# STHV800_pulser_board_v10.net
KiCad netlist of a schematic drawn in EAGLE
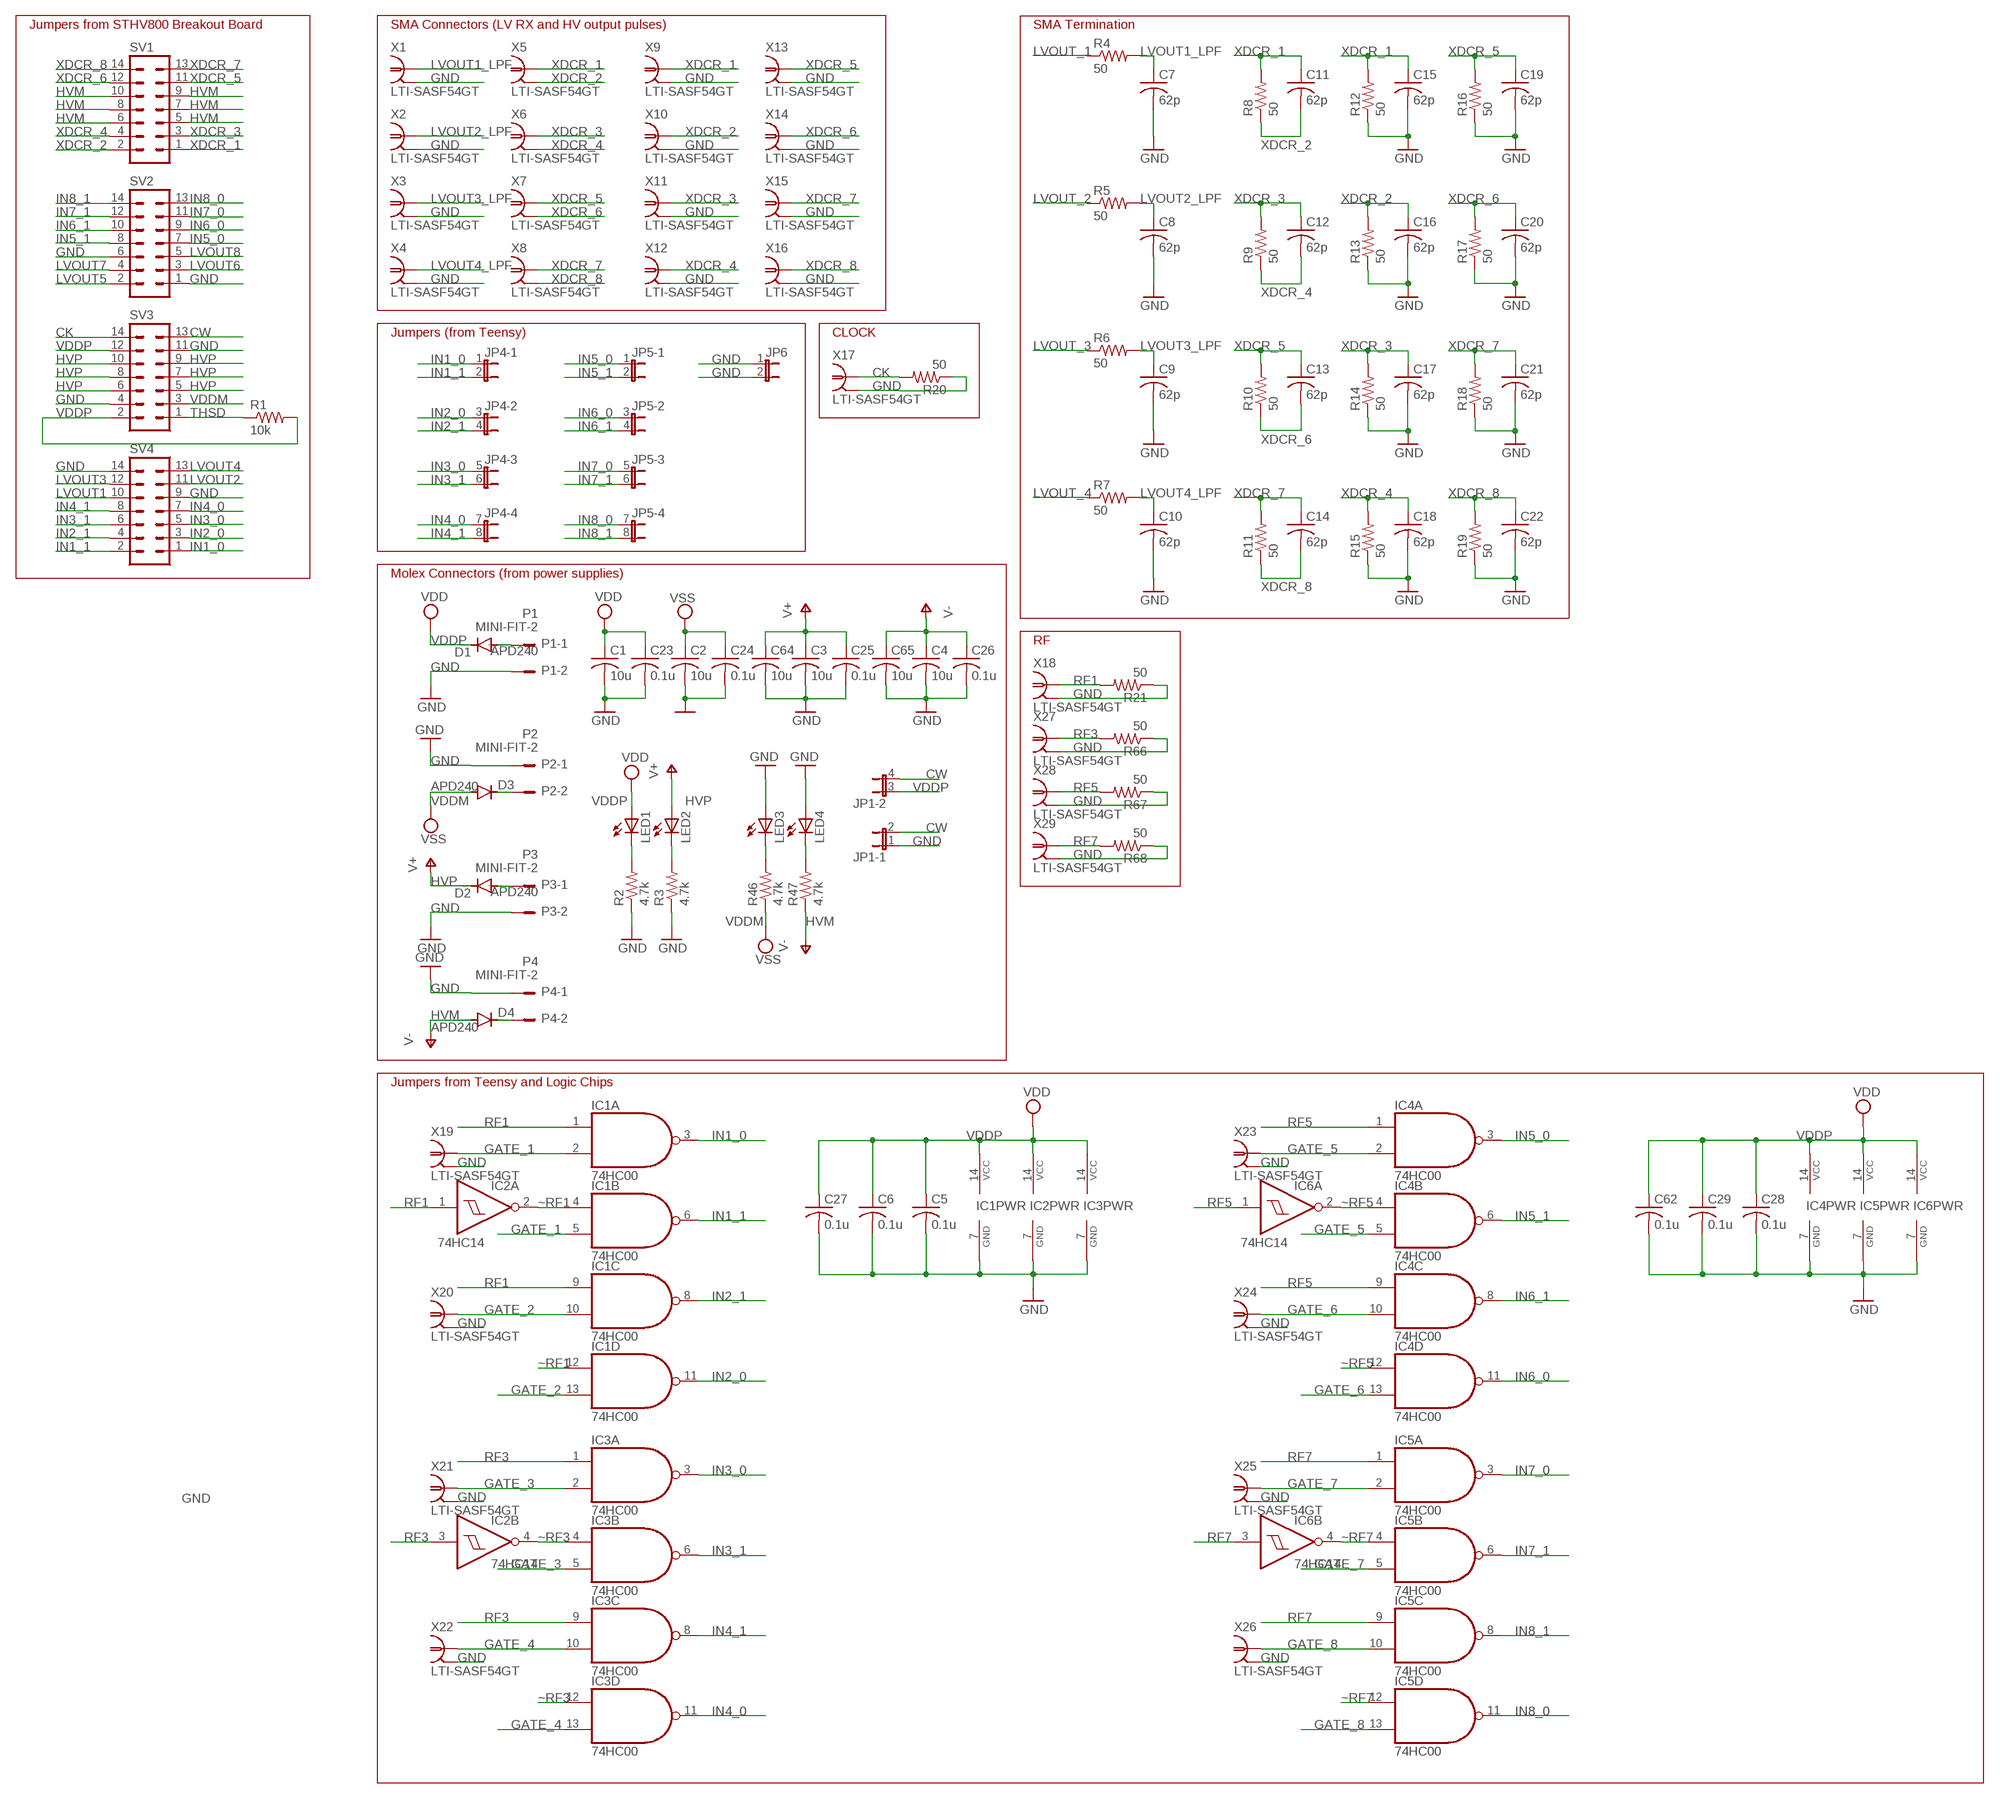
[diagram p0: schematic, sheet 1]
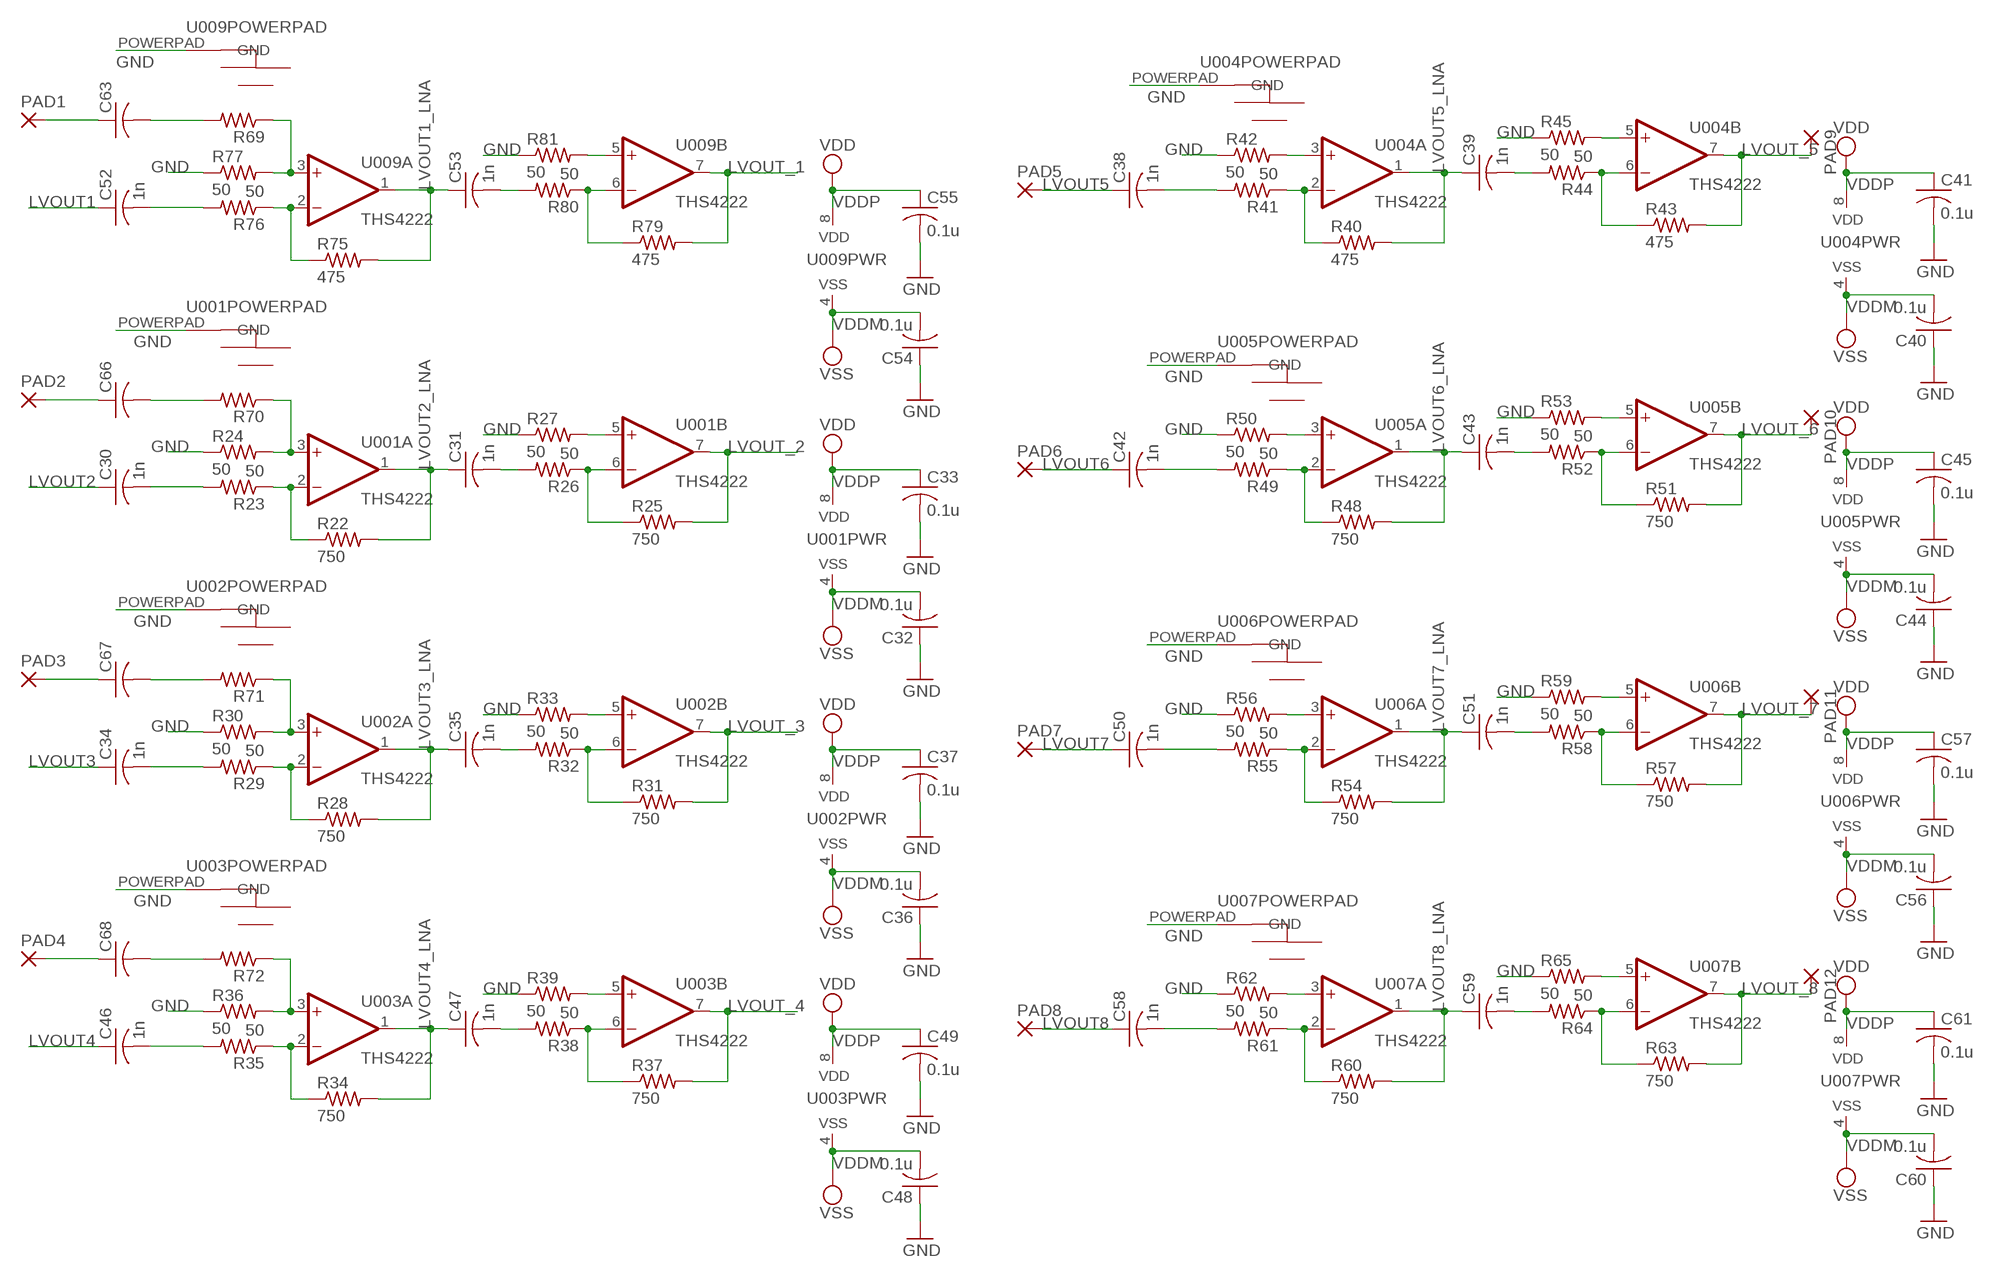
[diagram p1: schematic, sheet 2]

(export (version "E")
  (design (tool "Eeschema 10.0.6"))
  (components
    (comp (ref "C1")
      (value "10u")
      (footprint "eagle-import:C1206")
      (libsource (lib "eagle-import") (part "C-USC1206"))
    )
    (comp (ref "C2")
      (value "10u")
      (footprint "eagle-import:C1206")
      (libsource (lib "eagle-import") (part "C-USC1206"))
    )
    (comp (ref "C3")
      (value "10u")
      (footprint "eagle-import:C1210")
      (libsource (lib "eagle-import") (part "C-USC1210"))
    )
    (comp (ref "C4")
      (value "10u")
      (footprint "eagle-import:C1210")
      (libsource (lib "eagle-import") (part "C-USC1210"))
    )
    (comp (ref "C5")
      (value "0.1u")
      (footprint "eagle-import:C0805")
      (libsource (lib "eagle-import") (part "C-USC0805"))
    )
    (comp (ref "C6")
      (value "0.1u")
      (footprint "eagle-import:C0805")
      (libsource (lib "eagle-import") (part "C-USC0805"))
    )
    (comp (ref "C7")
      (value "62p")
      (footprint "eagle-import:C0805")
      (libsource (lib "eagle-import") (part "C-USC0805"))
    )
    (comp (ref "C8")
      (value "62p")
      (footprint "eagle-import:C0805")
      (libsource (lib "eagle-import") (part "C-USC0805"))
    )
    (comp (ref "C9")
      (value "62p")
      (footprint "eagle-import:C0805")
      (libsource (lib "eagle-import") (part "C-USC0805"))
    )
    (comp (ref "C10")
      (value "62p")
      (footprint "eagle-import:C0805")
      (libsource (lib "eagle-import") (part "C-USC0805"))
    )
    (comp (ref "C11")
      (value "62p")
      (footprint "eagle-import:C0805")
      (libsource (lib "eagle-import") (part "C-USC0805"))
    )
    (comp (ref "C12")
      (value "62p")
      (footprint "eagle-import:C0805")
      (libsource (lib "eagle-import") (part "C-USC0805"))
    )
    (comp (ref "C13")
      (value "62p")
      (footprint "eagle-import:C0805")
      (libsource (lib "eagle-import") (part "C-USC0805"))
    )
    (comp (ref "C14")
      (value "62p")
      (footprint "eagle-import:C0805")
      (libsource (lib "eagle-import") (part "C-USC0805"))
    )
    (comp (ref "C15")
      (value "62p")
      (footprint "eagle-import:C0805")
      (libsource (lib "eagle-import") (part "C-USC0805"))
    )
    (comp (ref "C16")
      (value "62p")
      (footprint "eagle-import:C0805")
      (libsource (lib "eagle-import") (part "C-USC0805"))
    )
    (comp (ref "C17")
      (value "62p")
      (footprint "eagle-import:C0805")
      (libsource (lib "eagle-import") (part "C-USC0805"))
    )
    (comp (ref "C18")
      (value "62p")
      (footprint "eagle-import:C0805")
      (libsource (lib "eagle-import") (part "C-USC0805"))
    )
    (comp (ref "C19")
      (value "62p")
      (footprint "eagle-import:C0805")
      (libsource (lib "eagle-import") (part "C-USC0805"))
    )
    (comp (ref "C20")
      (value "62p")
      (footprint "eagle-import:C0805")
      (libsource (lib "eagle-import") (part "C-USC0805"))
    )
    (comp (ref "C21")
      (value "62p")
      (footprint "eagle-import:C0805")
      (libsource (lib "eagle-import") (part "C-USC0805"))
    )
    (comp (ref "C22")
      (value "62p")
      (footprint "eagle-import:C0805")
      (libsource (lib "eagle-import") (part "C-USC0805"))
    )
    (comp (ref "C23")
      (value "0.1u")
      (footprint "eagle-import:C0805")
      (libsource (lib "eagle-import") (part "C-USC0805"))
    )
    (comp (ref "C24")
      (value "0.1u")
      (footprint "eagle-import:C0805")
      (libsource (lib "eagle-import") (part "C-USC0805"))
    )
    (comp (ref "C25")
      (value "0.1u")
      (footprint "eagle-import:C0805")
      (libsource (lib "eagle-import") (part "C-USC0805"))
    )
    (comp (ref "C26")
      (value "0.1u")
      (footprint "eagle-import:C0805")
      (libsource (lib "eagle-import") (part "C-USC0805"))
    )
    (comp (ref "C27")
      (value "0.1u")
      (footprint "eagle-import:C0805")
      (libsource (lib "eagle-import") (part "C-USC0805"))
    )
    (comp (ref "C28")
      (value "0.1u")
      (footprint "eagle-import:C0805")
      (libsource (lib "eagle-import") (part "C-USC0805"))
    )
    (comp (ref "C29")
      (value "0.1u")
      (footprint "eagle-import:C0805")
      (libsource (lib "eagle-import") (part "C-USC0805"))
    )
    (comp (ref "C62")
      (value "0.1u")
      (footprint "eagle-import:C0805")
      (libsource (lib "eagle-import") (part "C-USC0805"))
    )
    (comp (ref "C64")
      (value "10u")
      (footprint "eagle-import:C1210")
      (libsource (lib "eagle-import") (part "C-USC1210"))
    )
    (comp (ref "C65")
      (value "10u")
      (footprint "eagle-import:C1210")
      (libsource (lib "eagle-import") (part "C-USC1210"))
    )
    (comp (ref "D1")
      (value "APD240")
      (footprint "eagle-import:SOD-123_MINI-SMA")
      (libsource (lib "eagle-import") (part "CGRM400-G1"))
    )
    (comp (ref "D2")
      (value "APD240")
      (footprint "eagle-import:SOD-123_MINI-SMA")
      (libsource (lib "eagle-import") (part "CGRM400-G1"))
    )
    (comp (ref "D3")
      (value "APD240")
      (footprint "eagle-import:SOD-123_MINI-SMA")
      (libsource (lib "eagle-import") (part "CGRM400-G1"))
    )
    (comp (ref "D4")
      (value "APD240")
      (footprint "eagle-import:SOD-123_MINI-SMA")
      (libsource (lib "eagle-import") (part "CGRM400-G1"))
    )
    (comp (ref "IC1")
      (value "74HC00")
      (footprint "eagle-import:TSSOP14")
      (libsource (lib "eagle-import") (part "74HC00"))
    )
    (comp (ref "IC2")
      (value "74HC14")
      (footprint "eagle-import:TSSOP14")
      (libsource (lib "eagle-import") (part "74HC14"))
    )
    (comp (ref "IC3")
      (value "74HC00")
      (footprint "eagle-import:TSSOP14")
      (libsource (lib "eagle-import") (part "74HC00"))
    )
    (comp (ref "IC4")
      (value "74HC00")
      (footprint "eagle-import:TSSOP14")
      (libsource (lib "eagle-import") (part "74HC00"))
    )
    (comp (ref "IC5")
      (value "74HC00")
      (footprint "eagle-import:TSSOP14")
      (libsource (lib "eagle-import") (part "74HC00"))
    )
    (comp (ref "IC6")
      (value "74HC14")
      (footprint "eagle-import:TSSOP14")
      (libsource (lib "eagle-import") (part "74HC14"))
    )
    (comp (ref "JP1")
      (value "JP2QE")
      (footprint "eagle-import:JP2Q")
      (libsource (lib "eagle-import") (part "JP2QE"))
    )
    (comp (ref "JP4")
      (value "JP4QE")
      (footprint "eagle-import:JP4Q")
      (libsource (lib "eagle-import") (part "JP4QE"))
    )
    (comp (ref "JP5")
      (value "JP4QE")
      (footprint "eagle-import:JP4Q")
      (libsource (lib "eagle-import") (part "JP4QE"))
    )
    (comp (ref "JP6")
      (value "JP1E")
      (footprint "eagle-import:JP1")
      (libsource (lib "eagle-import") (part "JP1E"))
    )
    (comp (ref "LED1")
      (value "LEDSMT1206")
      (footprint "eagle-import:1206")
      (libsource (lib "eagle-import") (part "LEDSMT1206"))
    )
    (comp (ref "LED2")
      (value "LEDSMT1206")
      (footprint "eagle-import:1206")
      (libsource (lib "eagle-import") (part "LEDSMT1206"))
    )
    (comp (ref "LED3")
      (value "LEDSMT1206")
      (footprint "eagle-import:1206")
      (libsource (lib "eagle-import") (part "LEDSMT1206"))
    )
    (comp (ref "LED4")
      (value "LEDSMT1206")
      (footprint "eagle-import:1206")
      (libsource (lib "eagle-import") (part "LEDSMT1206"))
    )
    (comp (ref "P1")
      (value "MINI-FIT-2")
      (footprint "eagle-import:CON-MOLEX-MINI-FIT_39-30-_02_")
      (libsource (lib "eagle-import") (part "MINI-FIT-2"))
    )
    (comp (ref "P2")
      (value "MINI-FIT-2")
      (footprint "eagle-import:CON-MOLEX-MINI-FIT_39-30-_02_")
      (libsource (lib "eagle-import") (part "MINI-FIT-2"))
    )
    (comp (ref "P3")
      (value "MINI-FIT-2")
      (footprint "eagle-import:CON-MOLEX-MINI-FIT_39-30-_02_")
      (libsource (lib "eagle-import") (part "MINI-FIT-2"))
    )
    (comp (ref "P4")
      (value "MINI-FIT-2")
      (footprint "eagle-import:CON-MOLEX-MINI-FIT_39-30-_02_")
      (libsource (lib "eagle-import") (part "MINI-FIT-2"))
    )
    (comp (ref "R1")
      (value "10k")
      (footprint "eagle-import:R0805")
      (libsource (lib "eagle-import") (part "R-US_R0805"))
    )
    (comp (ref "R2")
      (value "4.7k")
      (footprint "eagle-import:R0805")
      (libsource (lib "eagle-import") (part "R-US_R0805"))
    )
    (comp (ref "R3")
      (value "4.7k")
      (footprint "eagle-import:R0805")
      (libsource (lib "eagle-import") (part "R-US_R0805"))
    )
    (comp (ref "R4")
      (value "50")
      (footprint "eagle-import:R1206")
      (libsource (lib "eagle-import") (part "R-US_R1206"))
    )
    (comp (ref "R5")
      (value "50")
      (footprint "eagle-import:R1206")
      (libsource (lib "eagle-import") (part "R-US_R1206"))
    )
    (comp (ref "R6")
      (value "50")
      (footprint "eagle-import:R1206")
      (libsource (lib "eagle-import") (part "R-US_R1206"))
    )
    (comp (ref "R7")
      (value "50")
      (footprint "eagle-import:R1206")
      (libsource (lib "eagle-import") (part "R-US_R1206"))
    )
    (comp (ref "R8")
      (value "50")
      (footprint "eagle-import:R1206")
      (libsource (lib "eagle-import") (part "R-US_R1206"))
    )
    (comp (ref "R9")
      (value "50")
      (footprint "eagle-import:R1206")
      (libsource (lib "eagle-import") (part "R-US_R1206"))
    )
    (comp (ref "R10")
      (value "50")
      (footprint "eagle-import:R1206")
      (libsource (lib "eagle-import") (part "R-US_R1206"))
    )
    (comp (ref "R11")
      (value "50")
      (footprint "eagle-import:R1206")
      (libsource (lib "eagle-import") (part "R-US_R1206"))
    )
    (comp (ref "R12")
      (value "50")
      (footprint "eagle-import:R1206")
      (libsource (lib "eagle-import") (part "R-US_R1206"))
    )
    (comp (ref "R13")
      (value "50")
      (footprint "eagle-import:R1206")
      (libsource (lib "eagle-import") (part "R-US_R1206"))
    )
    (comp (ref "R14")
      (value "50")
      (footprint "eagle-import:R1206")
      (libsource (lib "eagle-import") (part "R-US_R1206"))
    )
    (comp (ref "R15")
      (value "50")
      (footprint "eagle-import:R1206")
      (libsource (lib "eagle-import") (part "R-US_R1206"))
    )
    (comp (ref "R16")
      (value "50")
      (footprint "eagle-import:R1206")
      (libsource (lib "eagle-import") (part "R-US_R1206"))
    )
    (comp (ref "R17")
      (value "50")
      (footprint "eagle-import:R1206")
      (libsource (lib "eagle-import") (part "R-US_R1206"))
    )
    (comp (ref "R18")
      (value "50")
      (footprint "eagle-import:R1206")
      (libsource (lib "eagle-import") (part "R-US_R1206"))
    )
    (comp (ref "R19")
      (value "50")
      (footprint "eagle-import:R1206")
      (libsource (lib "eagle-import") (part "R-US_R1206"))
    )
    (comp (ref "R20")
      (value "50")
      (footprint "eagle-import:R0805")
      (libsource (lib "eagle-import") (part "R-US_R0805"))
    )
    (comp (ref "R21")
      (value "50")
      (footprint "eagle-import:R0805")
      (libsource (lib "eagle-import") (part "R-US_R0805"))
    )
    (comp (ref "R46")
      (value "4.7k")
      (footprint "eagle-import:R0805")
      (libsource (lib "eagle-import") (part "R-US_R0805"))
    )
    (comp (ref "R47")
      (value "4.7k")
      (footprint "eagle-import:R0805")
      (libsource (lib "eagle-import") (part "R-US_R0805"))
    )
    (comp (ref "R66")
      (value "50")
      (footprint "eagle-import:R0805")
      (libsource (lib "eagle-import") (part "R-US_R0805"))
    )
    (comp (ref "R67")
      (value "50")
      (footprint "eagle-import:R0805")
      (libsource (lib "eagle-import") (part "R-US_R0805"))
    )
    (comp (ref "R68")
      (value "50")
      (footprint "eagle-import:R0805")
      (libsource (lib "eagle-import") (part "R-US_R0805"))
    )
    (comp (ref "SV1")
      (value "MA07-2")
      (footprint "eagle-import:MA07-2")
      (libsource (lib "eagle-import") (part "MA07-2"))
    )
    (comp (ref "SV2")
      (value "MA07-2")
      (footprint "eagle-import:MA07-2")
      (libsource (lib "eagle-import") (part "MA07-2"))
    )
    (comp (ref "SV3")
      (value "MA07-2")
      (footprint "eagle-import:MA07-2")
      (libsource (lib "eagle-import") (part "MA07-2"))
    )
    (comp (ref "SV4")
      (value "MA07-2")
      (footprint "eagle-import:MA07-2")
      (libsource (lib "eagle-import") (part "MA07-2"))
    )
    (comp (ref "X1")
      (value "LTI-SASF54GT")
      (footprint "eagle-import:LTI-SASF54GT")
      (libsource (lib "eagle-import") (part "LTI-SASF54GT"))
    )
    (comp (ref "X2")
      (value "LTI-SASF54GT")
      (footprint "eagle-import:LTI-SASF54GT")
      (libsource (lib "eagle-import") (part "LTI-SASF54GT"))
    )
    (comp (ref "X3")
      (value "LTI-SASF54GT")
      (footprint "eagle-import:LTI-SASF54GT")
      (libsource (lib "eagle-import") (part "LTI-SASF54GT"))
    )
    (comp (ref "X4")
      (value "LTI-SASF54GT")
      (footprint "eagle-import:LTI-SASF54GT")
      (libsource (lib "eagle-import") (part "LTI-SASF54GT"))
    )
    (comp (ref "X5")
      (value "LTI-SASF54GT")
      (footprint "eagle-import:LTI-SASF54GT")
      (libsource (lib "eagle-import") (part "LTI-SASF54GT"))
    )
    (comp (ref "X6")
      (value "LTI-SASF54GT")
      (footprint "eagle-import:LTI-SASF54GT")
      (libsource (lib "eagle-import") (part "LTI-SASF54GT"))
    )
    (comp (ref "X7")
      (value "LTI-SASF54GT")
      (footprint "eagle-import:LTI-SASF54GT")
      (libsource (lib "eagle-import") (part "LTI-SASF54GT"))
    )
    (comp (ref "X8")
      (value "LTI-SASF54GT")
      (footprint "eagle-import:LTI-SASF54GT")
      (libsource (lib "eagle-import") (part "LTI-SASF54GT"))
    )
    (comp (ref "X9")
      (value "LTI-SASF54GT")
      (footprint "eagle-import:LTI-SASF54GT")
      (libsource (lib "eagle-import") (part "LTI-SASF54GT"))
    )
    (comp (ref "X10")
      (value "LTI-SASF54GT")
      (footprint "eagle-import:LTI-SASF54GT")
      (libsource (lib "eagle-import") (part "LTI-SASF54GT"))
    )
    (comp (ref "X11")
      (value "LTI-SASF54GT")
      (footprint "eagle-import:LTI-SASF54GT")
      (libsource (lib "eagle-import") (part "LTI-SASF54GT"))
    )
    (comp (ref "X12")
      (value "LTI-SASF54GT")
      (footprint "eagle-import:LTI-SASF54GT")
      (libsource (lib "eagle-import") (part "LTI-SASF54GT"))
    )
    (comp (ref "X13")
      (value "LTI-SASF54GT")
      (footprint "eagle-import:LTI-SASF54GT")
      (libsource (lib "eagle-import") (part "LTI-SASF54GT"))
    )
    (comp (ref "X14")
      (value "LTI-SASF54GT")
      (footprint "eagle-import:LTI-SASF54GT")
      (libsource (lib "eagle-import") (part "LTI-SASF54GT"))
    )
    (comp (ref "X15")
      (value "LTI-SASF54GT")
      (footprint "eagle-import:LTI-SASF54GT")
      (libsource (lib "eagle-import") (part "LTI-SASF54GT"))
    )
    (comp (ref "X16")
      (value "LTI-SASF54GT")
      (footprint "eagle-import:LTI-SASF54GT")
      (libsource (lib "eagle-import") (part "LTI-SASF54GT"))
    )
    (comp (ref "X17")
      (value "LTI-SASF54GT")
      (footprint "eagle-import:LTI-SASF54GT")
      (libsource (lib "eagle-import") (part "LTI-SASF54GT"))
    )
    (comp (ref "X18")
      (value "LTI-SASF54GT")
      (footprint "eagle-import:LTI-SASF54GT")
      (libsource (lib "eagle-import") (part "LTI-SASF54GT"))
    )
    (comp (ref "X19")
      (value "LTI-SASF54GT")
      (footprint "eagle-import:LTI-SASF54GT")
      (libsource (lib "eagle-import") (part "LTI-SASF54GT"))
    )
    (comp (ref "X20")
      (value "LTI-SASF54GT")
      (footprint "eagle-import:LTI-SASF54GT")
      (libsource (lib "eagle-import") (part "LTI-SASF54GT"))
    )
    (comp (ref "X21")
      (value "LTI-SASF54GT")
      (footprint "eagle-import:LTI-SASF54GT")
      (libsource (lib "eagle-import") (part "LTI-SASF54GT"))
    )
    (comp (ref "X22")
      (value "LTI-SASF54GT")
      (footprint "eagle-import:LTI-SASF54GT")
      (libsource (lib "eagle-import") (part "LTI-SASF54GT"))
    )
    (comp (ref "X23")
      (value "LTI-SASF54GT")
      (footprint "eagle-import:LTI-SASF54GT")
      (libsource (lib "eagle-import") (part "LTI-SASF54GT"))
    )
    (comp (ref "X24")
      (value "LTI-SASF54GT")
      (footprint "eagle-import:LTI-SASF54GT")
      (libsource (lib "eagle-import") (part "LTI-SASF54GT"))
    )
    (comp (ref "X25")
      (value "LTI-SASF54GT")
      (footprint "eagle-import:LTI-SASF54GT")
      (libsource (lib "eagle-import") (part "LTI-SASF54GT"))
    )
    (comp (ref "X26")
      (value "LTI-SASF54GT")
      (footprint "eagle-import:LTI-SASF54GT")
      (libsource (lib "eagle-import") (part "LTI-SASF54GT"))
    )
    (comp (ref "X27")
      (value "LTI-SASF54GT")
      (footprint "eagle-import:LTI-SASF54GT")
      (libsource (lib "eagle-import") (part "LTI-SASF54GT"))
    )
    (comp (ref "X28")
      (value "LTI-SASF54GT")
      (footprint "eagle-import:LTI-SASF54GT")
      (libsource (lib "eagle-import") (part "LTI-SASF54GT"))
    )
    (comp (ref "X29")
      (value "LTI-SASF54GT")
      (footprint "eagle-import:LTI-SASF54GT")
      (libsource (lib "eagle-import") (part "LTI-SASF54GT"))
    )
    (comp (ref "C30")
      (value "1n")
      (footprint "eagle-import:C0805")
      (libsource (lib "eagle-import") (part "C-USC0805"))
    )
    (comp (ref "C31")
      (value "1n")
      (footprint "eagle-import:C0805")
      (libsource (lib "eagle-import") (part "C-USC0805"))
    )
    (comp (ref "C32")
      (value "0.1u")
      (footprint "eagle-import:C0805")
      (libsource (lib "eagle-import") (part "C-USC0805"))
    )
    (comp (ref "C33")
      (value "0.1u")
      (footprint "eagle-import:C0805")
      (libsource (lib "eagle-import") (part "C-USC0805"))
    )
    (comp (ref "C34")
      (value "1n")
      (footprint "eagle-import:C0805")
      (libsource (lib "eagle-import") (part "C-USC0805"))
    )
    (comp (ref "C35")
      (value "1n")
      (footprint "eagle-import:C0805")
      (libsource (lib "eagle-import") (part "C-USC0805"))
    )
    (comp (ref "C36")
      (value "0.1u")
      (footprint "eagle-import:C0805")
      (libsource (lib "eagle-import") (part "C-USC0805"))
    )
    (comp (ref "C37")
      (value "0.1u")
      (footprint "eagle-import:C0805")
      (libsource (lib "eagle-import") (part "C-USC0805"))
    )
    (comp (ref "C38")
      (value "1n")
      (footprint "eagle-import:C0805")
      (libsource (lib "eagle-import") (part "C-USC0805"))
    )
    (comp (ref "C39")
      (value "1n")
      (footprint "eagle-import:C0805")
      (libsource (lib "eagle-import") (part "C-USC0805"))
    )
    (comp (ref "C40")
      (value "0.1u")
      (footprint "eagle-import:C0805")
      (libsource (lib "eagle-import") (part "C-USC0805"))
    )
    (comp (ref "C41")
      (value "0.1u")
      (footprint "eagle-import:C0805")
      (libsource (lib "eagle-import") (part "C-USC0805"))
    )
    (comp (ref "C42")
      (value "1n")
      (footprint "eagle-import:C0805")
      (libsource (lib "eagle-import") (part "C-USC0805"))
    )
    (comp (ref "C43")
      (value "1n")
      (footprint "eagle-import:C0805")
      (libsource (lib "eagle-import") (part "C-USC0805"))
    )
    (comp (ref "C44")
      (value "0.1u")
      (footprint "eagle-import:C0805")
      (libsource (lib "eagle-import") (part "C-USC0805"))
    )
    (comp (ref "C45")
      (value "0.1u")
      (footprint "eagle-import:C0805")
      (libsource (lib "eagle-import") (part "C-USC0805"))
    )
    (comp (ref "C46")
      (value "1n")
      (footprint "eagle-import:C0805")
      (libsource (lib "eagle-import") (part "C-USC0805"))
    )
    (comp (ref "C47")
      (value "1n")
      (footprint "eagle-import:C0805")
      (libsource (lib "eagle-import") (part "C-USC0805"))
    )
    (comp (ref "C48")
      (value "0.1u")
      (footprint "eagle-import:C0805")
      (libsource (lib "eagle-import") (part "C-USC0805"))
    )
    (comp (ref "C49")
      (value "0.1u")
      (footprint "eagle-import:C0805")
      (libsource (lib "eagle-import") (part "C-USC0805"))
    )
    (comp (ref "C50")
      (value "1n")
      (footprint "eagle-import:C0805")
      (libsource (lib "eagle-import") (part "C-USC0805"))
    )
    (comp (ref "C51")
      (value "1n")
      (footprint "eagle-import:C0805")
      (libsource (lib "eagle-import") (part "C-USC0805"))
    )
    (comp (ref "C52")
      (value "1n")
      (footprint "eagle-import:C0805")
      (libsource (lib "eagle-import") (part "C-USC0805"))
    )
    (comp (ref "C53")
      (value "1n")
      (footprint "eagle-import:C0805")
      (libsource (lib "eagle-import") (part "C-USC0805"))
    )
    (comp (ref "C54")
      (value "0.1u")
      (footprint "eagle-import:C0805")
      (libsource (lib "eagle-import") (part "C-USC0805"))
    )
    (comp (ref "C55")
      (value "0.1u")
      (footprint "eagle-import:C0805")
      (libsource (lib "eagle-import") (part "C-USC0805"))
    )
    (comp (ref "C56")
      (value "0.1u")
      (footprint "eagle-import:C0805")
      (libsource (lib "eagle-import") (part "C-USC0805"))
    )
    (comp (ref "C57")
      (value "0.1u")
      (footprint "eagle-import:C0805")
      (libsource (lib "eagle-import") (part "C-USC0805"))
    )
    (comp (ref "C58")
      (value "1n")
      (footprint "eagle-import:C0805")
      (libsource (lib "eagle-import") (part "C-USC0805"))
    )
    (comp (ref "C59")
      (value "1n")
      (footprint "eagle-import:C0805")
      (libsource (lib "eagle-import") (part "C-USC0805"))
    )
    (comp (ref "C60")
      (value "0.1u")
      (footprint "eagle-import:C0805")
      (libsource (lib "eagle-import") (part "C-USC0805"))
    )
    (comp (ref "C61")
      (value "0.1u")
      (footprint "eagle-import:C0805")
      (libsource (lib "eagle-import") (part "C-USC0805"))
    )
    (comp (ref "C63")
      (value "C-USC0805")
      (footprint "eagle-import:C0805")
      (libsource (lib "eagle-import") (part "C-USC0805"))
    )
    (comp (ref "C66")
      (value "C-USC0805")
      (footprint "eagle-import:C0805")
      (libsource (lib "eagle-import") (part "C-USC0805"))
    )
    (comp (ref "C67")
      (value "C-USC0805")
      (footprint "eagle-import:C0805")
      (libsource (lib "eagle-import") (part "C-USC0805"))
    )
    (comp (ref "C68")
      (value "C-USC0805")
      (footprint "eagle-import:C0805")
      (libsource (lib "eagle-import") (part "C-USC0805"))
    )
    (comp (ref "PAD1")
      (value "1,6/0,8")
      (footprint "eagle-import:1,6_0,8")
      (libsource (lib "eagle-import") (part "1,6/0,8"))
    )
    (comp (ref "PAD2")
      (value "1,6/0,8")
      (footprint "eagle-import:1,6_0,8")
      (libsource (lib "eagle-import") (part "1,6/0,8"))
    )
    (comp (ref "PAD3")
      (value "1,6/0,8")
      (footprint "eagle-import:1,6_0,8")
      (libsource (lib "eagle-import") (part "1,6/0,8"))
    )
    (comp (ref "PAD4")
      (value "1,6/0,8")
      (footprint "eagle-import:1,6_0,8")
      (libsource (lib "eagle-import") (part "1,6/0,8"))
    )
    (comp (ref "PAD5")
      (value "1,6/0,8")
      (footprint "eagle-import:1,6_0,8")
      (libsource (lib "eagle-import") (part "1,6/0,8"))
    )
    (comp (ref "PAD6")
      (value "1,6/0,8")
      (footprint "eagle-import:1,6_0,8")
      (libsource (lib "eagle-import") (part "1,6/0,8"))
    )
    (comp (ref "PAD7")
      (value "1,6/0,8")
      (footprint "eagle-import:1,6_0,8")
      (libsource (lib "eagle-import") (part "1,6/0,8"))
    )
    (comp (ref "PAD8")
      (value "1,6/0,8")
      (footprint "eagle-import:1,6_0,8")
      (libsource (lib "eagle-import") (part "1,6/0,8"))
    )
    (comp (ref "PAD9")
      (value "1,6/0,8")
      (footprint "eagle-import:1,6_0,8")
      (libsource (lib "eagle-import") (part "1,6/0,8"))
    )
    (comp (ref "PAD10")
      (value "1,6/0,8")
      (footprint "eagle-import:1,6_0,8")
      (libsource (lib "eagle-import") (part "1,6/0,8"))
    )
    (comp (ref "PAD11")
      (value "1,6/0,8")
      (footprint "eagle-import:1,6_0,8")
      (libsource (lib "eagle-import") (part "1,6/0,8"))
    )
    (comp (ref "PAD12")
      (value "1,6/0,8")
      (footprint "eagle-import:1,6_0,8")
      (libsource (lib "eagle-import") (part "1,6/0,8"))
    )
    (comp (ref "R22")
      (value "750")
      (footprint "eagle-import:R0805")
      (libsource (lib "eagle-import") (part "R-US_R0805"))
    )
    (comp (ref "R23")
      (value "50")
      (footprint "eagle-import:R0805")
      (libsource (lib "eagle-import") (part "R-US_R0805"))
    )
    (comp (ref "R24")
      (value "50")
      (footprint "eagle-import:R0805")
      (libsource (lib "eagle-import") (part "R-US_R0805"))
    )
    (comp (ref "R25")
      (value "750")
      (footprint "eagle-import:R0805")
      (libsource (lib "eagle-import") (part "R-US_R0805"))
    )
    (comp (ref "R26")
      (value "50")
      (footprint "eagle-import:R0805")
      (libsource (lib "eagle-import") (part "R-US_R0805"))
    )
    (comp (ref "R27")
      (value "50")
      (footprint "eagle-import:R0805")
      (libsource (lib "eagle-import") (part "R-US_R0805"))
    )
    (comp (ref "R28")
      (value "750")
      (footprint "eagle-import:R0805")
      (libsource (lib "eagle-import") (part "R-US_R0805"))
    )
    (comp (ref "R29")
      (value "50")
      (footprint "eagle-import:R0805")
      (libsource (lib "eagle-import") (part "R-US_R0805"))
    )
    (comp (ref "R30")
      (value "50")
      (footprint "eagle-import:R0805")
      (libsource (lib "eagle-import") (part "R-US_R0805"))
    )
    (comp (ref "R31")
      (value "750")
      (footprint "eagle-import:R0805")
      (libsource (lib "eagle-import") (part "R-US_R0805"))
    )
    (comp (ref "R32")
      (value "50")
      (footprint "eagle-import:R0805")
      (libsource (lib "eagle-import") (part "R-US_R0805"))
    )
    (comp (ref "R33")
      (value "50")
      (footprint "eagle-import:R0805")
      (libsource (lib "eagle-import") (part "R-US_R0805"))
    )
    (comp (ref "R34")
      (value "750")
      (footprint "eagle-import:R0805")
      (libsource (lib "eagle-import") (part "R-US_R0805"))
    )
    (comp (ref "R35")
      (value "50")
      (footprint "eagle-import:R0805")
      (libsource (lib "eagle-import") (part "R-US_R0805"))
    )
    (comp (ref "R36")
      (value "50")
      (footprint "eagle-import:R0805")
      (libsource (lib "eagle-import") (part "R-US_R0805"))
    )
    (comp (ref "R37")
      (value "750")
      (footprint "eagle-import:R0805")
      (libsource (lib "eagle-import") (part "R-US_R0805"))
    )
    (comp (ref "R38")
      (value "50")
      (footprint "eagle-import:R0805")
      (libsource (lib "eagle-import") (part "R-US_R0805"))
    )
    (comp (ref "R39")
      (value "50")
      (footprint "eagle-import:R0805")
      (libsource (lib "eagle-import") (part "R-US_R0805"))
    )
    (comp (ref "R40")
      (value "475")
      (footprint "eagle-import:R0805")
      (libsource (lib "eagle-import") (part "R-US_R0805"))
    )
    (comp (ref "R41")
      (value "50")
      (footprint "eagle-import:R0805")
      (libsource (lib "eagle-import") (part "R-US_R0805"))
    )
    (comp (ref "R42")
      (value "50")
      (footprint "eagle-import:R0805")
      (libsource (lib "eagle-import") (part "R-US_R0805"))
    )
    (comp (ref "R43")
      (value "475")
      (footprint "eagle-import:R0805")
      (libsource (lib "eagle-import") (part "R-US_R0805"))
    )
    (comp (ref "R44")
      (value "50")
      (footprint "eagle-import:R0805")
      (libsource (lib "eagle-import") (part "R-US_R0805"))
    )
    (comp (ref "R45")
      (value "50")
      (footprint "eagle-import:R0805")
      (libsource (lib "eagle-import") (part "R-US_R0805"))
    )
    (comp (ref "R48")
      (value "750")
      (footprint "eagle-import:R0805")
      (libsource (lib "eagle-import") (part "R-US_R0805"))
    )
    (comp (ref "R49")
      (value "50")
      (footprint "eagle-import:R0805")
      (libsource (lib "eagle-import") (part "R-US_R0805"))
    )
    (comp (ref "R50")
      (value "50")
      (footprint "eagle-import:R0805")
      (libsource (lib "eagle-import") (part "R-US_R0805"))
    )
    (comp (ref "R51")
      (value "750")
      (footprint "eagle-import:R0805")
      (libsource (lib "eagle-import") (part "R-US_R0805"))
    )
    (comp (ref "R52")
      (value "50")
      (footprint "eagle-import:R0805")
      (libsource (lib "eagle-import") (part "R-US_R0805"))
    )
    (comp (ref "R53")
      (value "50")
      (footprint "eagle-import:R0805")
      (libsource (lib "eagle-import") (part "R-US_R0805"))
    )
    (comp (ref "R54")
      (value "750")
      (footprint "eagle-import:R0805")
      (libsource (lib "eagle-import") (part "R-US_R0805"))
    )
    (comp (ref "R55")
      (value "50")
      (footprint "eagle-import:R0805")
      (libsource (lib "eagle-import") (part "R-US_R0805"))
    )
    (comp (ref "R56")
      (value "50")
      (footprint "eagle-import:R0805")
      (libsource (lib "eagle-import") (part "R-US_R0805"))
    )
    (comp (ref "R57")
      (value "750")
      (footprint "eagle-import:R0805")
      (libsource (lib "eagle-import") (part "R-US_R0805"))
    )
    (comp (ref "R58")
      (value "50")
      (footprint "eagle-import:R0805")
      (libsource (lib "eagle-import") (part "R-US_R0805"))
    )
    (comp (ref "R59")
      (value "50")
      (footprint "eagle-import:R0805")
      (libsource (lib "eagle-import") (part "R-US_R0805"))
    )
    (comp (ref "R60")
      (value "750")
      (footprint "eagle-import:R0805")
      (libsource (lib "eagle-import") (part "R-US_R0805"))
    )
    (comp (ref "R61")
      (value "50")
      (footprint "eagle-import:R0805")
      (libsource (lib "eagle-import") (part "R-US_R0805"))
    )
    (comp (ref "R62")
      (value "50")
      (footprint "eagle-import:R0805")
      (libsource (lib "eagle-import") (part "R-US_R0805"))
    )
    (comp (ref "R63")
      (value "750")
      (footprint "eagle-import:R0805")
      (libsource (lib "eagle-import") (part "R-US_R0805"))
    )
    (comp (ref "R64")
      (value "50")
      (footprint "eagle-import:R0805")
      (libsource (lib "eagle-import") (part "R-US_R0805"))
    )
    (comp (ref "R65")
      (value "50")
      (footprint "eagle-import:R0805")
      (libsource (lib "eagle-import") (part "R-US_R0805"))
    )
    (comp (ref "R69")
      (value "R-US_R0805")
      (footprint "eagle-import:R0805")
      (libsource (lib "eagle-import") (part "R-US_R0805"))
    )
    (comp (ref "R70")
      (value "R-US_R0805")
      (footprint "eagle-import:R0805")
      (libsource (lib "eagle-import") (part "R-US_R0805"))
    )
    (comp (ref "R71")
      (value "R-US_R0805")
      (footprint "eagle-import:R0805")
      (libsource (lib "eagle-import") (part "R-US_R0805"))
    )
    (comp (ref "R72")
      (value "R-US_R0805")
      (footprint "eagle-import:R0805")
      (libsource (lib "eagle-import") (part "R-US_R0805"))
    )
    (comp (ref "R75")
      (value "475")
      (footprint "eagle-import:R0805")
      (libsource (lib "eagle-import") (part "R-US_R0805"))
    )
    (comp (ref "R76")
      (value "50")
      (footprint "eagle-import:R0805")
      (libsource (lib "eagle-import") (part "R-US_R0805"))
    )
    (comp (ref "R77")
      (value "50")
      (footprint "eagle-import:R0805")
      (libsource (lib "eagle-import") (part "R-US_R0805"))
    )
    (comp (ref "R79")
      (value "475")
      (footprint "eagle-import:R0805")
      (libsource (lib "eagle-import") (part "R-US_R0805"))
    )
    (comp (ref "R80")
      (value "50")
      (footprint "eagle-import:R0805")
      (libsource (lib "eagle-import") (part "R-US_R0805"))
    )
    (comp (ref "R81")
      (value "50")
      (footprint "eagle-import:R0805")
      (libsource (lib "eagle-import") (part "R-US_R0805"))
    )
    (comp (ref "U001")
      (value "THS4222")
      (footprint "eagle-import:SSOP08-POWERPAD")
      (libsource (lib "eagle-import") (part "THS4222"))
    )
    (comp (ref "U002")
      (value "THS4222")
      (footprint "eagle-import:SSOP08-POWERPAD")
      (libsource (lib "eagle-import") (part "THS4222"))
    )
    (comp (ref "U003")
      (value "THS4222")
      (footprint "eagle-import:SSOP08-POWERPAD")
      (libsource (lib "eagle-import") (part "THS4222"))
    )
    (comp (ref "U004")
      (value "THS4222")
      (footprint "eagle-import:SSOP08-POWERPAD")
      (libsource (lib "eagle-import") (part "THS4222"))
    )
    (comp (ref "U005")
      (value "THS4222")
      (footprint "eagle-import:SSOP08-POWERPAD")
      (libsource (lib "eagle-import") (part "THS4222"))
    )
    (comp (ref "U006")
      (value "THS4222")
      (footprint "eagle-import:SSOP08-POWERPAD")
      (libsource (lib "eagle-import") (part "THS4222"))
    )
    (comp (ref "U007")
      (value "THS4222")
      (footprint "eagle-import:SSOP08-POWERPAD")
      (libsource (lib "eagle-import") (part "THS4222"))
    )
    (comp (ref "U009")
      (value "THS4222")
      (footprint "eagle-import:SSOP08-POWERPAD")
      (libsource (lib "eagle-import") (part "THS4222"))
    )
  )
  (nets
    (net (code "1") (name "CK") (class "Default")
      (node (ref "R20") (pin "2") (pinfunction "2_2") (pintype "passive"))
      (node (ref "SV3") (pin "14") (pinfunction "14_14") (pintype "passive"))
      (node (ref "X17") (pin "1") (pinfunction "1_1") (pintype "passive"))
    )
    (net (code "2") (name "CW") (class "Default")
      (node (ref "JP1") (pin "2") (pinfunction "2_2") (pintype "passive"))
      (node (ref "JP1") (pin "4") (pinfunction "2_4") (pintype "passive"))
      (node (ref "SV3") (pin "13") (pinfunction "13_13") (pintype "passive"))
    )
    (net (code "3") (name "GATE_1") (class "Default")
      (node (ref "IC1") (pin "2") (pinfunction "I1_2") (pintype "input"))
      (node (ref "IC1") (pin "5") (pinfunction "I1_5") (pintype "input"))
      (node (ref "X19") (pin "1") (pinfunction "1_1") (pintype "passive"))
    )
    (net (code "4") (name "GATE_2") (class "Default")
      (node (ref "IC1") (pin "10") (pinfunction "I1_10") (pintype "input"))
      (node (ref "IC1") (pin "13") (pinfunction "I1_13") (pintype "input"))
      (node (ref "X20") (pin "1") (pinfunction "1_1") (pintype "passive"))
    )
    (net (code "5") (name "GATE_3") (class "Default")
      (node (ref "IC3") (pin "2") (pinfunction "I1_2") (pintype "input"))
      (node (ref "IC3") (pin "5") (pinfunction "I1_5") (pintype "input"))
      (node (ref "X21") (pin "1") (pinfunction "1_1") (pintype "passive"))
    )
    (net (code "6") (name "GATE_4") (class "Default")
      (node (ref "IC3") (pin "10") (pinfunction "I1_10") (pintype "input"))
      (node (ref "IC3") (pin "13") (pinfunction "I1_13") (pintype "input"))
      (node (ref "X22") (pin "1") (pinfunction "1_1") (pintype "passive"))
    )
    (net (code "7") (name "GATE_5") (class "Default")
      (node (ref "IC4") (pin "2") (pinfunction "I1_2") (pintype "input"))
      (node (ref "IC4") (pin "5") (pinfunction "I1_5") (pintype "input"))
      (node (ref "X23") (pin "1") (pinfunction "1_1") (pintype "passive"))
    )
    (net (code "8") (name "GATE_6") (class "Default")
      (node (ref "IC4") (pin "10") (pinfunction "I1_10") (pintype "input"))
      (node (ref "IC4") (pin "13") (pinfunction "I1_13") (pintype "input"))
      (node (ref "X24") (pin "1") (pinfunction "1_1") (pintype "passive"))
    )
    (net (code "9") (name "GATE_7") (class "Default")
      (node (ref "IC5") (pin "2") (pinfunction "I1_2") (pintype "input"))
      (node (ref "IC5") (pin "5") (pinfunction "I1_5") (pintype "input"))
      (node (ref "X25") (pin "1") (pinfunction "1_1") (pintype "passive"))
    )
    (net (code "10") (name "GATE_8") (class "Default")
      (node (ref "IC5") (pin "10") (pinfunction "I1_10") (pintype "input"))
      (node (ref "IC5") (pin "13") (pinfunction "I1_13") (pintype "input"))
      (node (ref "X26") (pin "1") (pinfunction "1_1") (pintype "passive"))
    )
    (net (code "11") (name "GND") (class "Default")
      (node (ref "C1") (pin "2") (pinfunction "2_2") (pintype "passive"))
      (node (ref "C10") (pin "2") (pinfunction "2_2") (pintype "passive"))
      (node (ref "C15") (pin "2") (pinfunction "2_2") (pintype "passive"))
      (node (ref "C16") (pin "2") (pinfunction "2_2") (pintype "passive"))
      (node (ref "C17") (pin "2") (pinfunction "2_2") (pintype "passive"))
      (node (ref "C18") (pin "2") (pinfunction "2_2") (pintype "passive"))
      (node (ref "C19") (pin "2") (pinfunction "2_2") (pintype "passive"))
      (node (ref "C2") (pin "2") (pinfunction "2_2") (pintype "passive"))
      (node (ref "C20") (pin "2") (pinfunction "2_2") (pintype "passive"))
      (node (ref "C21") (pin "2") (pinfunction "2_2") (pintype "passive"))
      (node (ref "C22") (pin "2") (pinfunction "2_2") (pintype "passive"))
      (node (ref "C23") (pin "2") (pinfunction "2_2") (pintype "passive"))
      (node (ref "C24") (pin "2") (pinfunction "2_2") (pintype "passive"))
      (node (ref "C25") (pin "2") (pinfunction "2_2") (pintype "passive"))
      (node (ref "C26") (pin "2") (pinfunction "2_2") (pintype "passive"))
      (node (ref "C27") (pin "2") (pinfunction "2_2") (pintype "passive"))
      (node (ref "C28") (pin "2") (pinfunction "2_2") (pintype "passive"))
      (node (ref "C29") (pin "2") (pinfunction "2_2") (pintype "passive"))
      (node (ref "C3") (pin "2") (pinfunction "2_2") (pintype "passive"))
      (node (ref "C32") (pin "1") (pinfunction "1_1") (pintype "passive"))
      (node (ref "C33") (pin "2") (pinfunction "2_2") (pintype "passive"))
      (node (ref "C36") (pin "1") (pinfunction "1_1") (pintype "passive"))
      (node (ref "C37") (pin "2") (pinfunction "2_2") (pintype "passive"))
      (node (ref "C4") (pin "2") (pinfunction "2_2") (pintype "passive"))
      (node (ref "C40") (pin "1") (pinfunction "1_1") (pintype "passive"))
      (node (ref "C41") (pin "2") (pinfunction "2_2") (pintype "passive"))
      (node (ref "C44") (pin "1") (pinfunction "1_1") (pintype "passive"))
      (node (ref "C45") (pin "2") (pinfunction "2_2") (pintype "passive"))
      (node (ref "C48") (pin "1") (pinfunction "1_1") (pintype "passive"))
      (node (ref "C49") (pin "2") (pinfunction "2_2") (pintype "passive"))
      (node (ref "C5") (pin "2") (pinfunction "2_2") (pintype "passive"))
      (node (ref "C54") (pin "1") (pinfunction "1_1") (pintype "passive"))
      (node (ref "C55") (pin "2") (pinfunction "2_2") (pintype "passive"))
      (node (ref "C56") (pin "1") (pinfunction "1_1") (pintype "passive"))
      (node (ref "C57") (pin "2") (pinfunction "2_2") (pintype "passive"))
      (node (ref "C6") (pin "2") (pinfunction "2_2") (pintype "passive"))
      (node (ref "C60") (pin "1") (pinfunction "1_1") (pintype "passive"))
      (node (ref "C61") (pin "2") (pinfunction "2_2") (pintype "passive"))
      (node (ref "C62") (pin "2") (pinfunction "2_2") (pintype "passive"))
      (node (ref "C64") (pin "2") (pinfunction "2_2") (pintype "passive"))
      (node (ref "C65") (pin "2") (pinfunction "2_2") (pintype "passive"))
      (node (ref "C7") (pin "2") (pinfunction "2_2") (pintype "passive"))
      (node (ref "C8") (pin "2") (pinfunction "2_2") (pintype "passive"))
      (node (ref "C9") (pin "2") (pinfunction "2_2") (pintype "passive"))
      (node (ref "IC1") (pin "7") (pinfunction "GND_7") (pintype "power_in"))
      (node (ref "IC2") (pin "7") (pinfunction "GND_7") (pintype "power_in"))
      (node (ref "IC3") (pin "7") (pinfunction "GND_7") (pintype "power_in"))
      (node (ref "IC4") (pin "7") (pinfunction "GND_7") (pintype "power_in"))
      (node (ref "IC5") (pin "7") (pinfunction "GND_7") (pintype "power_in"))
      (node (ref "IC6") (pin "7") (pinfunction "GND_7") (pintype "power_in"))
      (node (ref "JP1") (pin "1") (pinfunction "1_1") (pintype "passive"))
      (node (ref "JP6") (pin "1") (pinfunction "1_1") (pintype "passive"))
      (node (ref "JP6") (pin "2") (pinfunction "2_2") (pintype "passive"))
      (node (ref "LED3") (pin "A") (pinfunction "A_A") (pintype "passive"))
      (node (ref "LED4") (pin "A") (pinfunction "A_A") (pintype "passive"))
      (node (ref "P1") (pin "2") (pinfunction "P_2") (pintype "passive"))
      (node (ref "P2") (pin "1") (pinfunction "P_1") (pintype "passive"))
      (node (ref "P3") (pin "2") (pinfunction "P_2") (pintype "passive"))
      (node (ref "P4") (pin "1") (pinfunction "P_1") (pintype "passive"))
      (node (ref "R12") (pin "1") (pinfunction "1_1") (pintype "passive"))
      (node (ref "R13") (pin "1") (pinfunction "1_1") (pintype "passive"))
      (node (ref "R14") (pin "1") (pinfunction "1_1") (pintype "passive"))
      (node (ref "R15") (pin "1") (pinfunction "1_1") (pintype "passive"))
      (node (ref "R16") (pin "1") (pinfunction "1_1") (pintype "passive"))
      (node (ref "R17") (pin "1") (pinfunction "1_1") (pintype "passive"))
      (node (ref "R18") (pin "1") (pinfunction "1_1") (pintype "passive"))
      (node (ref "R19") (pin "1") (pinfunction "1_1") (pintype "passive"))
      (node (ref "R2") (pin "1") (pinfunction "1_1") (pintype "passive"))
      (node (ref "R20") (pin "1") (pinfunction "1_1") (pintype "passive"))
      (node (ref "R21") (pin "1") (pinfunction "1_1") (pintype "passive"))
      (node (ref "R24") (pin "1") (pinfunction "1_1") (pintype "passive"))
      (node (ref "R27") (pin "1") (pinfunction "1_1") (pintype "passive"))
      (node (ref "R3") (pin "1") (pinfunction "1_1") (pintype "passive"))
      (node (ref "R30") (pin "1") (pinfunction "1_1") (pintype "passive"))
      (node (ref "R33") (pin "1") (pinfunction "1_1") (pintype "passive"))
      (node (ref "R36") (pin "1") (pinfunction "1_1") (pintype "passive"))
      (node (ref "R39") (pin "1") (pinfunction "1_1") (pintype "passive"))
      (node (ref "R42") (pin "1") (pinfunction "1_1") (pintype "passive"))
      (node (ref "R45") (pin "1") (pinfunction "1_1") (pintype "passive"))
      (node (ref "R50") (pin "1") (pinfunction "1_1") (pintype "passive"))
      (node (ref "R53") (pin "1") (pinfunction "1_1") (pintype "passive"))
      (node (ref "R56") (pin "1") (pinfunction "1_1") (pintype "passive"))
      (node (ref "R59") (pin "1") (pinfunction "1_1") (pintype "passive"))
      (node (ref "R62") (pin "1") (pinfunction "1_1") (pintype "passive"))
      (node (ref "R65") (pin "1") (pinfunction "1_1") (pintype "passive"))
      (node (ref "R66") (pin "1") (pinfunction "1_1") (pintype "passive"))
      (node (ref "R67") (pin "1") (pinfunction "1_1") (pintype "passive"))
      (node (ref "R68") (pin "1") (pinfunction "1_1") (pintype "passive"))
      (node (ref "R77") (pin "1") (pinfunction "1_1") (pintype "passive"))
      (node (ref "R81") (pin "1") (pinfunction "1_1") (pintype "passive"))
      (node (ref "SV2") (pin "1") (pinfunction "1_1") (pintype "passive"))
      (node (ref "SV2") (pin "6") (pinfunction "6_6") (pintype "passive"))
      (node (ref "SV3") (pin "11") (pinfunction "11_11") (pintype "passive"))
      (node (ref "SV3") (pin "4") (pinfunction "4_4") (pintype "passive"))
      (node (ref "SV4") (pin "14") (pinfunction "14_14") (pintype "passive"))
      (node (ref "SV4") (pin "9") (pinfunction "9_9") (pintype "passive"))
      (node (ref "U001") (pin "POWERPAD") (pinfunction "GND_POWERPAD") (pintype "power_in"))
      (node (ref "U002") (pin "POWERPAD") (pinfunction "GND_POWERPAD") (pintype "power_in"))
      (node (ref "U003") (pin "POWERPAD") (pinfunction "GND_POWERPAD") (pintype "power_in"))
      (node (ref "U004") (pin "POWERPAD") (pinfunction "GND_POWERPAD") (pintype "power_in"))
      (node (ref "U005") (pin "POWERPAD") (pinfunction "GND_POWERPAD") (pintype "power_in"))
      (node (ref "U006") (pin "POWERPAD") (pinfunction "GND_POWERPAD") (pintype "power_in"))
      (node (ref "U007") (pin "POWERPAD") (pinfunction "GND_POWERPAD") (pintype "power_in"))
      (node (ref "U009") (pin "POWERPAD") (pinfunction "GND_POWERPAD") (pintype "power_in"))
      (node (ref "X1") (pin "2") (pinfunction "2_2") (pintype "passive"))
      (node (ref "X1") (pin "3") (pinfunction "2_3") (pintype "passive"))
      (node (ref "X1") (pin "4") (pinfunction "2_4") (pintype "passive"))
      (node (ref "X1") (pin "5") (pinfunction "2_5") (pintype "passive"))
      (node (ref "X10") (pin "2") (pinfunction "2_2") (pintype "passive"))
      (node (ref "X10") (pin "3") (pinfunction "2_3") (pintype "passive"))
      (node (ref "X10") (pin "4") (pinfunction "2_4") (pintype "passive"))
      (node (ref "X10") (pin "5") (pinfunction "2_5") (pintype "passive"))
      (node (ref "X11") (pin "2") (pinfunction "2_2") (pintype "passive"))
      (node (ref "X11") (pin "3") (pinfunction "2_3") (pintype "passive"))
      (node (ref "X11") (pin "4") (pinfunction "2_4") (pintype "passive"))
      (node (ref "X11") (pin "5") (pinfunction "2_5") (pintype "passive"))
      (node (ref "X12") (pin "2") (pinfunction "2_2") (pintype "passive"))
      (node (ref "X12") (pin "3") (pinfunction "2_3") (pintype "passive"))
      (node (ref "X12") (pin "4") (pinfunction "2_4") (pintype "passive"))
      (node (ref "X12") (pin "5") (pinfunction "2_5") (pintype "passive"))
      (node (ref "X13") (pin "2") (pinfunction "2_2") (pintype "passive"))
      (node (ref "X13") (pin "3") (pinfunction "2_3") (pintype "passive"))
      (node (ref "X13") (pin "4") (pinfunction "2_4") (pintype "passive"))
      (node (ref "X13") (pin "5") (pinfunction "2_5") (pintype "passive"))
      (node (ref "X14") (pin "2") (pinfunction "2_2") (pintype "passive"))
      (node (ref "X14") (pin "3") (pinfunction "2_3") (pintype "passive"))
      (node (ref "X14") (pin "4") (pinfunction "2_4") (pintype "passive"))
      (node (ref "X14") (pin "5") (pinfunction "2_5") (pintype "passive"))
      (node (ref "X15") (pin "2") (pinfunction "2_2") (pintype "passive"))
      (node (ref "X15") (pin "3") (pinfunction "2_3") (pintype "passive"))
      (node (ref "X15") (pin "4") (pinfunction "2_4") (pintype "passive"))
      (node (ref "X15") (pin "5") (pinfunction "2_5") (pintype "passive"))
      (node (ref "X16") (pin "2") (pinfunction "2_2") (pintype "passive"))
      (node (ref "X16") (pin "3") (pinfunction "2_3") (pintype "passive"))
      (node (ref "X16") (pin "4") (pinfunction "2_4") (pintype "passive"))
      (node (ref "X16") (pin "5") (pinfunction "2_5") (pintype "passive"))
      (node (ref "X17") (pin "2") (pinfunction "2_2") (pintype "passive"))
      (node (ref "X17") (pin "3") (pinfunction "2_3") (pintype "passive"))
      (node (ref "X17") (pin "4") (pinfunction "2_4") (pintype "passive"))
      (node (ref "X17") (pin "5") (pinfunction "2_5") (pintype "passive"))
      (node (ref "X18") (pin "2") (pinfunction "2_2") (pintype "passive"))
      (node (ref "X18") (pin "3") (pinfunction "2_3") (pintype "passive"))
      (node (ref "X18") (pin "4") (pinfunction "2_4") (pintype "passive"))
      (node (ref "X18") (pin "5") (pinfunction "2_5") (pintype "passive"))
      (node (ref "X19") (pin "2") (pinfunction "2_2") (pintype "passive"))
      (node (ref "X19") (pin "3") (pinfunction "2_3") (pintype "passive"))
      (node (ref "X19") (pin "4") (pinfunction "2_4") (pintype "passive"))
      (node (ref "X19") (pin "5") (pinfunction "2_5") (pintype "passive"))
      (node (ref "X2") (pin "2") (pinfunction "2_2") (pintype "passive"))
      (node (ref "X2") (pin "3") (pinfunction "2_3") (pintype "passive"))
      (node (ref "X2") (pin "4") (pinfunction "2_4") (pintype "passive"))
      (node (ref "X2") (pin "5") (pinfunction "2_5") (pintype "passive"))
      (node (ref "X20") (pin "2") (pinfunction "2_2") (pintype "passive"))
      (node (ref "X20") (pin "3") (pinfunction "2_3") (pintype "passive"))
      (node (ref "X20") (pin "4") (pinfunction "2_4") (pintype "passive"))
      (node (ref "X20") (pin "5") (pinfunction "2_5") (pintype "passive"))
      (node (ref "X21") (pin "2") (pinfunction "2_2") (pintype "passive"))
      (node (ref "X21") (pin "3") (pinfunction "2_3") (pintype "passive"))
      (node (ref "X21") (pin "4") (pinfunction "2_4") (pintype "passive"))
      (node (ref "X21") (pin "5") (pinfunction "2_5") (pintype "passive"))
      (node (ref "X22") (pin "2") (pinfunction "2_2") (pintype "passive"))
      (node (ref "X22") (pin "3") (pinfunction "2_3") (pintype "passive"))
      (node (ref "X22") (pin "4") (pinfunction "2_4") (pintype "passive"))
      (node (ref "X22") (pin "5") (pinfunction "2_5") (pintype "passive"))
      (node (ref "X23") (pin "2") (pinfunction "2_2") (pintype "passive"))
      (node (ref "X23") (pin "3") (pinfunction "2_3") (pintype "passive"))
      (node (ref "X23") (pin "4") (pinfunction "2_4") (pintype "passive"))
      (node (ref "X23") (pin "5") (pinfunction "2_5") (pintype "passive"))
      (node (ref "X24") (pin "2") (pinfunction "2_2") (pintype "passive"))
      (node (ref "X24") (pin "3") (pinfunction "2_3") (pintype "passive"))
      (node (ref "X24") (pin "4") (pinfunction "2_4") (pintype "passive"))
      (node (ref "X24") (pin "5") (pinfunction "2_5") (pintype "passive"))
      (node (ref "X25") (pin "2") (pinfunction "2_2") (pintype "passive"))
      (node (ref "X25") (pin "3") (pinfunction "2_3") (pintype "passive"))
      (node (ref "X25") (pin "4") (pinfunction "2_4") (pintype "passive"))
      (node (ref "X25") (pin "5") (pinfunction "2_5") (pintype "passive"))
      (node (ref "X26") (pin "2") (pinfunction "2_2") (pintype "passive"))
      (node (ref "X26") (pin "3") (pinfunction "2_3") (pintype "passive"))
      (node (ref "X26") (pin "4") (pinfunction "2_4") (pintype "passive"))
      (node (ref "X26") (pin "5") (pinfunction "2_5") (pintype "passive"))
      (node (ref "X27") (pin "2") (pinfunction "2_2") (pintype "passive"))
      (node (ref "X27") (pin "3") (pinfunction "2_3") (pintype "passive"))
      (node (ref "X27") (pin "4") (pinfunction "2_4") (pintype "passive"))
      (node (ref "X27") (pin "5") (pinfunction "2_5") (pintype "passive"))
      (node (ref "X28") (pin "2") (pinfunction "2_2") (pintype "passive"))
      (node (ref "X28") (pin "3") (pinfunction "2_3") (pintype "passive"))
      (node (ref "X28") (pin "4") (pinfunction "2_4") (pintype "passive"))
      (node (ref "X28") (pin "5") (pinfunction "2_5") (pintype "passive"))
      (node (ref "X29") (pin "2") (pinfunction "2_2") (pintype "passive"))
      (node (ref "X29") (pin "3") (pinfunction "2_3") (pintype "passive"))
      (node (ref "X29") (pin "4") (pinfunction "2_4") (pintype "passive"))
      (node (ref "X29") (pin "5") (pinfunction "2_5") (pintype "passive"))
      (node (ref "X3") (pin "2") (pinfunction "2_2") (pintype "passive"))
      (node (ref "X3") (pin "3") (pinfunction "2_3") (pintype "passive"))
      (node (ref "X3") (pin "4") (pinfunction "2_4") (pintype "passive"))
      (node (ref "X3") (pin "5") (pinfunction "2_5") (pintype "passive"))
      (node (ref "X4") (pin "2") (pinfunction "2_2") (pintype "passive"))
      (node (ref "X4") (pin "3") (pinfunction "2_3") (pintype "passive"))
      (node (ref "X4") (pin "4") (pinfunction "2_4") (pintype "passive"))
      (node (ref "X4") (pin "5") (pinfunction "2_5") (pintype "passive"))
      (node (ref "X9") (pin "2") (pinfunction "2_2") (pintype "passive"))
      (node (ref "X9") (pin "3") (pinfunction "2_3") (pintype "passive"))
      (node (ref "X9") (pin "4") (pinfunction "2_4") (pintype "passive"))
      (node (ref "X9") (pin "5") (pinfunction "2_5") (pintype "passive"))
    )
    (net (code "12") (name "HVM") (class "Default")
      (node (ref "C26") (pin "1") (pinfunction "1_1") (pintype "passive"))
      (node (ref "C4") (pin "1") (pinfunction "1_1") (pintype "passive"))
      (node (ref "C65") (pin "1") (pinfunction "1_1") (pintype "passive"))
      (node (ref "D4") (pin "A") (pinfunction "A_A") (pintype "passive"))
      (node (ref "R47") (pin "1") (pinfunction "1_1") (pintype "passive"))
      (node (ref "SV1") (pin "10") (pinfunction "10_10") (pintype "passive"))
      (node (ref "SV1") (pin "5") (pinfunction "5_5") (pintype "passive"))
      (node (ref "SV1") (pin "6") (pinfunction "6_6") (pintype "passive"))
      (node (ref "SV1") (pin "7") (pinfunction "7_7") (pintype "passive"))
      (node (ref "SV1") (pin "8") (pinfunction "8_8") (pintype "passive"))
      (node (ref "SV1") (pin "9") (pinfunction "9_9") (pintype "passive"))
    )
    (net (code "13") (name "HVP") (class "Default")
      (node (ref "C25") (pin "1") (pinfunction "1_1") (pintype "passive"))
      (node (ref "C3") (pin "1") (pinfunction "1_1") (pintype "passive"))
      (node (ref "C64") (pin "1") (pinfunction "1_1") (pintype "passive"))
      (node (ref "D2") (pin "C") (pinfunction "C_C") (pintype "passive"))
      (node (ref "LED2") (pin "A") (pinfunction "A_A") (pintype "passive"))
      (node (ref "SV3") (pin "10") (pinfunction "10_10") (pintype "passive"))
      (node (ref "SV3") (pin "5") (pinfunction "5_5") (pintype "passive"))
      (node (ref "SV3") (pin "6") (pinfunction "6_6") (pintype "passive"))
      (node (ref "SV3") (pin "7") (pinfunction "7_7") (pintype "passive"))
      (node (ref "SV3") (pin "8") (pinfunction "8_8") (pintype "passive"))
      (node (ref "SV3") (pin "9") (pinfunction "9_9") (pintype "passive"))
    )
    (net (code "14") (name "IN1_0") (class "Default")
      (node (ref "IC1") (pin "3") (pinfunction "O_3") (pintype "output"))
      (node (ref "JP4") (pin "1") (pinfunction "1_1") (pintype "passive"))
      (node (ref "SV4") (pin "1") (pinfunction "1_1") (pintype "passive"))
    )
    (net (code "15") (name "IN1_1") (class "Default")
      (node (ref "IC1") (pin "6") (pinfunction "O_6") (pintype "output"))
      (node (ref "JP4") (pin "2") (pinfunction "2_2") (pintype "passive"))
      (node (ref "SV4") (pin "2") (pinfunction "2_2") (pintype "passive"))
    )
    (net (code "16") (name "IN2_0") (class "Default")
      (node (ref "IC1") (pin "11") (pinfunction "O_11") (pintype "output"))
      (node (ref "JP4") (pin "3") (pinfunction "1_3") (pintype "passive"))
      (node (ref "SV4") (pin "3") (pinfunction "3_3") (pintype "passive"))
    )
    (net (code "17") (name "IN2_1") (class "Default")
      (node (ref "IC1") (pin "8") (pinfunction "O_8") (pintype "output"))
      (node (ref "JP4") (pin "4") (pinfunction "2_4") (pintype "passive"))
      (node (ref "SV4") (pin "4") (pinfunction "4_4") (pintype "passive"))
    )
    (net (code "18") (name "IN3_0") (class "Default")
      (node (ref "IC3") (pin "3") (pinfunction "O_3") (pintype "output"))
      (node (ref "JP4") (pin "5") (pinfunction "1_5") (pintype "passive"))
      (node (ref "SV4") (pin "5") (pinfunction "5_5") (pintype "passive"))
    )
    (net (code "19") (name "IN3_1") (class "Default")
      (node (ref "IC3") (pin "6") (pinfunction "O_6") (pintype "output"))
      (node (ref "JP4") (pin "6") (pinfunction "2_6") (pintype "passive"))
      (node (ref "SV4") (pin "6") (pinfunction "6_6") (pintype "passive"))
    )
    (net (code "20") (name "IN4_0") (class "Default")
      (node (ref "IC3") (pin "11") (pinfunction "O_11") (pintype "output"))
      (node (ref "JP4") (pin "7") (pinfunction "1_7") (pintype "passive"))
      (node (ref "SV4") (pin "7") (pinfunction "7_7") (pintype "passive"))
    )
    (net (code "21") (name "IN4_1") (class "Default")
      (node (ref "IC3") (pin "8") (pinfunction "O_8") (pintype "output"))
      (node (ref "JP4") (pin "8") (pinfunction "2_8") (pintype "passive"))
      (node (ref "SV4") (pin "8") (pinfunction "8_8") (pintype "passive"))
    )
    (net (code "22") (name "IN5_0") (class "Default")
      (node (ref "IC4") (pin "3") (pinfunction "O_3") (pintype "output"))
      (node (ref "JP5") (pin "1") (pinfunction "1_1") (pintype "passive"))
      (node (ref "SV2") (pin "7") (pinfunction "7_7") (pintype "passive"))
    )
    (net (code "23") (name "IN5_1") (class "Default")
      (node (ref "IC4") (pin "6") (pinfunction "O_6") (pintype "output"))
      (node (ref "JP5") (pin "2") (pinfunction "2_2") (pintype "passive"))
      (node (ref "SV2") (pin "8") (pinfunction "8_8") (pintype "passive"))
    )
    (net (code "24") (name "IN6_0") (class "Default")
      (node (ref "IC4") (pin "11") (pinfunction "O_11") (pintype "output"))
      (node (ref "JP5") (pin "3") (pinfunction "1_3") (pintype "passive"))
      (node (ref "SV2") (pin "9") (pinfunction "9_9") (pintype "passive"))
    )
    (net (code "25") (name "IN6_1") (class "Default")
      (node (ref "IC4") (pin "8") (pinfunction "O_8") (pintype "output"))
      (node (ref "JP5") (pin "4") (pinfunction "2_4") (pintype "passive"))
      (node (ref "SV2") (pin "10") (pinfunction "10_10") (pintype "passive"))
    )
    (net (code "26") (name "IN7_0") (class "Default")
      (node (ref "IC5") (pin "3") (pinfunction "O_3") (pintype "output"))
      (node (ref "JP5") (pin "5") (pinfunction "1_5") (pintype "passive"))
      (node (ref "SV2") (pin "11") (pinfunction "11_11") (pintype "passive"))
    )
    (net (code "27") (name "IN7_1") (class "Default")
      (node (ref "IC5") (pin "6") (pinfunction "O_6") (pintype "output"))
      (node (ref "JP5") (pin "6") (pinfunction "2_6") (pintype "passive"))
      (node (ref "SV2") (pin "12") (pinfunction "12_12") (pintype "passive"))
    )
    (net (code "28") (name "IN8_0") (class "Default")
      (node (ref "IC5") (pin "11") (pinfunction "O_11") (pintype "output"))
      (node (ref "JP5") (pin "7") (pinfunction "1_7") (pintype "passive"))
      (node (ref "SV2") (pin "13") (pinfunction "13_13") (pintype "passive"))
    )
    (net (code "29") (name "IN8_1") (class "Default")
      (node (ref "IC5") (pin "8") (pinfunction "O_8") (pintype "output"))
      (node (ref "JP5") (pin "8") (pinfunction "2_8") (pintype "passive"))
      (node (ref "SV2") (pin "14") (pinfunction "14_14") (pintype "passive"))
    )
    (net (code "30") (name "LVOUT1") (class "Default")
      (node (ref "C52") (pin "1") (pinfunction "1_1") (pintype "passive"))
      (node (ref "SV4") (pin "10") (pinfunction "10_10") (pintype "passive"))
    )
    (net (code "31") (name "LVOUT1_LNA") (class "Default")
      (node (ref "C53") (pin "1") (pinfunction "1_1") (pintype "passive"))
      (node (ref "R75") (pin "2") (pinfunction "2_2") (pintype "passive"))
      (node (ref "U009") (pin "1") (pinfunction "OUT_1") (pintype "output"))
    )
    (net (code "32") (name "LVOUT1_LPF") (class "Default")
      (node (ref "C7") (pin "1") (pinfunction "1_1") (pintype "passive"))
      (node (ref "R4") (pin "2") (pinfunction "2_2") (pintype "passive"))
      (node (ref "X1") (pin "1") (pinfunction "1_1") (pintype "passive"))
    )
    (net (code "33") (name "LVOUT2") (class "Default")
      (node (ref "C30") (pin "1") (pinfunction "1_1") (pintype "passive"))
      (node (ref "SV4") (pin "11") (pinfunction "11_11") (pintype "passive"))
    )
    (net (code "34") (name "LVOUT2_LNA") (class "Default")
      (node (ref "C31") (pin "1") (pinfunction "1_1") (pintype "passive"))
      (node (ref "R22") (pin "2") (pinfunction "2_2") (pintype "passive"))
      (node (ref "U001") (pin "1") (pinfunction "OUT_1") (pintype "output"))
    )
    (net (code "35") (name "LVOUT2_LPF") (class "Default")
      (node (ref "C8") (pin "1") (pinfunction "1_1") (pintype "passive"))
      (node (ref "R5") (pin "2") (pinfunction "2_2") (pintype "passive"))
      (node (ref "X2") (pin "1") (pinfunction "1_1") (pintype "passive"))
    )
    (net (code "36") (name "LVOUT3") (class "Default")
      (node (ref "C34") (pin "1") (pinfunction "1_1") (pintype "passive"))
      (node (ref "SV4") (pin "12") (pinfunction "12_12") (pintype "passive"))
    )
    (net (code "37") (name "LVOUT3_LNA") (class "Default")
      (node (ref "C35") (pin "1") (pinfunction "1_1") (pintype "passive"))
      (node (ref "R28") (pin "2") (pinfunction "2_2") (pintype "passive"))
      (node (ref "U002") (pin "1") (pinfunction "OUT_1") (pintype "output"))
    )
    (net (code "38") (name "LVOUT3_LPF") (class "Default")
      (node (ref "C9") (pin "1") (pinfunction "1_1") (pintype "passive"))
      (node (ref "R6") (pin "2") (pinfunction "2_2") (pintype "passive"))
      (node (ref "X3") (pin "1") (pinfunction "1_1") (pintype "passive"))
    )
    (net (code "39") (name "LVOUT4") (class "Default")
      (node (ref "C46") (pin "1") (pinfunction "1_1") (pintype "passive"))
      (node (ref "SV4") (pin "13") (pinfunction "13_13") (pintype "passive"))
    )
    (net (code "40") (name "LVOUT4_LNA") (class "Default")
      (node (ref "C47") (pin "1") (pinfunction "1_1") (pintype "passive"))
      (node (ref "R34") (pin "2") (pinfunction "2_2") (pintype "passive"))
      (node (ref "U003") (pin "1") (pinfunction "OUT_1") (pintype "output"))
    )
    (net (code "41") (name "LVOUT4_LPF") (class "Default")
      (node (ref "C10") (pin "1") (pinfunction "1_1") (pintype "passive"))
      (node (ref "R7") (pin "2") (pinfunction "2_2") (pintype "passive"))
      (node (ref "X4") (pin "1") (pinfunction "1_1") (pintype "passive"))
    )
    (net (code "42") (name "LVOUT5") (class "Default")
      (node (ref "C38") (pin "1") (pinfunction "1_1") (pintype "passive"))
      (node (ref "PAD5") (pin "1") (pinfunction "P_1") (pintype "passive"))
      (node (ref "SV2") (pin "2") (pinfunction "2_2") (pintype "passive"))
    )
    (net (code "43") (name "LVOUT5_LNA") (class "Default")
      (node (ref "C39") (pin "1") (pinfunction "1_1") (pintype "passive"))
      (node (ref "R40") (pin "2") (pinfunction "2_2") (pintype "passive"))
      (node (ref "U004") (pin "1") (pinfunction "OUT_1") (pintype "output"))
    )
    (net (code "44") (name "LVOUT6") (class "Default")
      (node (ref "C42") (pin "1") (pinfunction "1_1") (pintype "passive"))
      (node (ref "PAD6") (pin "1") (pinfunction "P_1") (pintype "passive"))
      (node (ref "SV2") (pin "3") (pinfunction "3_3") (pintype "passive"))
    )
    (net (code "45") (name "LVOUT6_LNA") (class "Default")
      (node (ref "C43") (pin "1") (pinfunction "1_1") (pintype "passive"))
      (node (ref "R48") (pin "2") (pinfunction "2_2") (pintype "passive"))
      (node (ref "U005") (pin "1") (pinfunction "OUT_1") (pintype "output"))
    )
    (net (code "46") (name "LVOUT7") (class "Default")
      (node (ref "C50") (pin "1") (pinfunction "1_1") (pintype "passive"))
      (node (ref "PAD7") (pin "1") (pinfunction "P_1") (pintype "passive"))
      (node (ref "SV2") (pin "4") (pinfunction "4_4") (pintype "passive"))
    )
    (net (code "47") (name "LVOUT7_LNA") (class "Default")
      (node (ref "C51") (pin "1") (pinfunction "1_1") (pintype "passive"))
      (node (ref "R54") (pin "2") (pinfunction "2_2") (pintype "passive"))
      (node (ref "U006") (pin "1") (pinfunction "OUT_1") (pintype "output"))
    )
    (net (code "48") (name "LVOUT8") (class "Default")
      (node (ref "C58") (pin "1") (pinfunction "1_1") (pintype "passive"))
      (node (ref "PAD8") (pin "1") (pinfunction "P_1") (pintype "passive"))
      (node (ref "SV2") (pin "5") (pinfunction "5_5") (pintype "passive"))
    )
    (net (code "49") (name "LVOUT8_LNA") (class "Default")
      (node (ref "C59") (pin "1") (pinfunction "1_1") (pintype "passive"))
      (node (ref "R60") (pin "2") (pinfunction "2_2") (pintype "passive"))
      (node (ref "U007") (pin "1") (pinfunction "OUT_1") (pintype "output"))
    )
    (net (code "50") (name "LVOUT_1") (class "Default")
      (node (ref "R4") (pin "1") (pinfunction "1_1") (pintype "passive"))
      (node (ref "R79") (pin "2") (pinfunction "2_2") (pintype "passive"))
      (node (ref "U009") (pin "7") (pinfunction "OUT_7") (pintype "output"))
    )
    (net (code "51") (name "LVOUT_2") (class "Default")
      (node (ref "R25") (pin "2") (pinfunction "2_2") (pintype "passive"))
      (node (ref "R5") (pin "1") (pinfunction "1_1") (pintype "passive"))
      (node (ref "U001") (pin "7") (pinfunction "OUT_7") (pintype "output"))
    )
    (net (code "52") (name "LVOUT_3") (class "Default")
      (node (ref "R31") (pin "2") (pinfunction "2_2") (pintype "passive"))
      (node (ref "R6") (pin "1") (pinfunction "1_1") (pintype "passive"))
      (node (ref "U002") (pin "7") (pinfunction "OUT_7") (pintype "output"))
    )
    (net (code "53") (name "LVOUT_4") (class "Default")
      (node (ref "R37") (pin "2") (pinfunction "2_2") (pintype "passive"))
      (node (ref "R7") (pin "1") (pinfunction "1_1") (pintype "passive"))
      (node (ref "U003") (pin "7") (pinfunction "OUT_7") (pintype "output"))
    )
    (net (code "54") (name "LVOUT_5") (class "Default")
      (node (ref "PAD9") (pin "1") (pinfunction "P_1") (pintype "passive"))
      (node (ref "R43") (pin "2") (pinfunction "2_2") (pintype "passive"))
      (node (ref "U004") (pin "7") (pinfunction "OUT_7") (pintype "output"))
    )
    (net (code "55") (name "LVOUT_6") (class "Default")
      (node (ref "PAD10") (pin "1") (pinfunction "P_1") (pintype "passive"))
      (node (ref "R51") (pin "2") (pinfunction "2_2") (pintype "passive"))
      (node (ref "U005") (pin "7") (pinfunction "OUT_7") (pintype "output"))
    )
    (net (code "56") (name "LVOUT_7") (class "Default")
      (node (ref "PAD11") (pin "1") (pinfunction "P_1") (pintype "passive"))
      (node (ref "R57") (pin "2") (pinfunction "2_2") (pintype "passive"))
      (node (ref "U006") (pin "7") (pinfunction "OUT_7") (pintype "output"))
    )
    (net (code "57") (name "LVOUT_8") (class "Default")
      (node (ref "PAD12") (pin "1") (pinfunction "P_1") (pintype "passive"))
      (node (ref "R63") (pin "2") (pinfunction "2_2") (pintype "passive"))
      (node (ref "U007") (pin "7") (pinfunction "OUT_7") (pintype "output"))
    )
    (net (code "58") (name "Net-(C30-Pad2)") (class "Default")
      (node (ref "C30") (pin "2") (pinfunction "2_2") (pintype "passive"))
      (node (ref "R23") (pin "2") (pinfunction "2_2") (pintype "passive"))
    )
    (net (code "59") (name "Net-(C31-Pad2)") (class "Default")
      (node (ref "C31") (pin "2") (pinfunction "2_2") (pintype "passive"))
      (node (ref "R26") (pin "2") (pinfunction "2_2") (pintype "passive"))
    )
    (net (code "60") (name "Net-(C34-Pad2)") (class "Default")
      (node (ref "C34") (pin "2") (pinfunction "2_2") (pintype "passive"))
      (node (ref "R29") (pin "2") (pinfunction "2_2") (pintype "passive"))
    )
    (net (code "61") (name "Net-(C35-Pad2)") (class "Default")
      (node (ref "C35") (pin "2") (pinfunction "2_2") (pintype "passive"))
      (node (ref "R32") (pin "2") (pinfunction "2_2") (pintype "passive"))
    )
    (net (code "62") (name "Net-(C38-Pad2)") (class "Default")
      (node (ref "C38") (pin "2") (pinfunction "2_2") (pintype "passive"))
      (node (ref "R41") (pin "2") (pinfunction "2_2") (pintype "passive"))
    )
    (net (code "63") (name "Net-(C39-Pad2)") (class "Default")
      (node (ref "C39") (pin "2") (pinfunction "2_2") (pintype "passive"))
      (node (ref "R44") (pin "2") (pinfunction "2_2") (pintype "passive"))
    )
    (net (code "64") (name "Net-(C42-Pad2)") (class "Default")
      (node (ref "C42") (pin "2") (pinfunction "2_2") (pintype "passive"))
      (node (ref "R49") (pin "2") (pinfunction "2_2") (pintype "passive"))
    )
    (net (code "65") (name "Net-(C43-Pad2)") (class "Default")
      (node (ref "C43") (pin "2") (pinfunction "2_2") (pintype "passive"))
      (node (ref "R52") (pin "2") (pinfunction "2_2") (pintype "passive"))
    )
    (net (code "66") (name "Net-(C46-Pad2)") (class "Default")
      (node (ref "C46") (pin "2") (pinfunction "2_2") (pintype "passive"))
      (node (ref "R35") (pin "2") (pinfunction "2_2") (pintype "passive"))
    )
    (net (code "67") (name "Net-(C47-Pad2)") (class "Default")
      (node (ref "C47") (pin "2") (pinfunction "2_2") (pintype "passive"))
      (node (ref "R38") (pin "2") (pinfunction "2_2") (pintype "passive"))
    )
    (net (code "68") (name "Net-(C50-Pad2)") (class "Default")
      (node (ref "C50") (pin "2") (pinfunction "2_2") (pintype "passive"))
      (node (ref "R55") (pin "2") (pinfunction "2_2") (pintype "passive"))
    )
    (net (code "69") (name "Net-(C51-Pad2)") (class "Default")
      (node (ref "C51") (pin "2") (pinfunction "2_2") (pintype "passive"))
      (node (ref "R58") (pin "2") (pinfunction "2_2") (pintype "passive"))
    )
    (net (code "70") (name "Net-(C52-Pad2)") (class "Default")
      (node (ref "C52") (pin "2") (pinfunction "2_2") (pintype "passive"))
      (node (ref "R76") (pin "2") (pinfunction "2_2") (pintype "passive"))
    )
    (net (code "71") (name "Net-(C53-Pad2)") (class "Default")
      (node (ref "C53") (pin "2") (pinfunction "2_2") (pintype "passive"))
      (node (ref "R80") (pin "2") (pinfunction "2_2") (pintype "passive"))
    )
    (net (code "72") (name "Net-(C58-Pad2)") (class "Default")
      (node (ref "C58") (pin "2") (pinfunction "2_2") (pintype "passive"))
      (node (ref "R61") (pin "2") (pinfunction "2_2") (pintype "passive"))
    )
    (net (code "73") (name "Net-(C59-Pad2)") (class "Default")
      (node (ref "C59") (pin "2") (pinfunction "2_2") (pintype "passive"))
      (node (ref "R64") (pin "2") (pinfunction "2_2") (pintype "passive"))
    )
    (net (code "74") (name "Net-(C63-Pad2)") (class "Default")
      (node (ref "C63") (pin "2") (pinfunction "2_2") (pintype "passive"))
      (node (ref "R69") (pin "2") (pinfunction "2_2") (pintype "passive"))
    )
    (net (code "75") (name "Net-(C66-Pad2)") (class "Default")
      (node (ref "C66") (pin "2") (pinfunction "2_2") (pintype "passive"))
      (node (ref "R70") (pin "2") (pinfunction "2_2") (pintype "passive"))
    )
    (net (code "76") (name "Net-(C67-Pad2)") (class "Default")
      (node (ref "C67") (pin "2") (pinfunction "2_2") (pintype "passive"))
      (node (ref "R71") (pin "2") (pinfunction "2_2") (pintype "passive"))
    )
    (net (code "77") (name "Net-(C68-Pad2)") (class "Default")
      (node (ref "C68") (pin "2") (pinfunction "2_2") (pintype "passive"))
      (node (ref "R72") (pin "2") (pinfunction "2_2") (pintype "passive"))
    )
    (net (code "78") (name "Net-(LED1-PadC)") (class "Default")
      (node (ref "LED1") (pin "C") (pinfunction "C_C") (pintype "passive"))
      (node (ref "R2") (pin "2") (pinfunction "2_2") (pintype "passive"))
    )
    (net (code "79") (name "Net-(LED2-PadC)") (class "Default")
      (node (ref "LED2") (pin "C") (pinfunction "C_C") (pintype "passive"))
      (node (ref "R3") (pin "2") (pinfunction "2_2") (pintype "passive"))
    )
    (net (code "80") (name "Net-(LED3-PadC)") (class "Default")
      (node (ref "LED3") (pin "C") (pinfunction "C_C") (pintype "passive"))
      (node (ref "R46") (pin "2") (pinfunction "2_2") (pintype "passive"))
    )
    (net (code "81") (name "Net-(LED4-PadC)") (class "Default")
      (node (ref "LED4") (pin "C") (pinfunction "C_C") (pintype "passive"))
      (node (ref "R47") (pin "2") (pinfunction "2_2") (pintype "passive"))
    )
    (net (code "82") (name "Net-(P1A-P)") (class "Default")
      (node (ref "D1") (pin "A") (pinfunction "A_A") (pintype "passive"))
      (node (ref "P1") (pin "1") (pinfunction "P_1") (pintype "passive"))
    )
    (net (code "83") (name "Net-(P2B-P)") (class "Default")
      (node (ref "D3") (pin "C") (pinfunction "C_C") (pintype "passive"))
      (node (ref "P2") (pin "2") (pinfunction "P_2") (pintype "passive"))
    )
    (net (code "84") (name "Net-(P3A-P)") (class "Default")
      (node (ref "D2") (pin "A") (pinfunction "A_A") (pintype "passive"))
      (node (ref "P3") (pin "1") (pinfunction "P_1") (pintype "passive"))
    )
    (net (code "85") (name "Net-(P4B-P)") (class "Default")
      (node (ref "D4") (pin "C") (pinfunction "C_C") (pintype "passive"))
      (node (ref "P4") (pin "2") (pinfunction "P_2") (pintype "passive"))
    )
    (net (code "86") (name "Net-(PAD1-P)") (class "Default")
      (node (ref "C63") (pin "1") (pinfunction "1_1") (pintype "passive"))
      (node (ref "PAD1") (pin "1") (pinfunction "P_1") (pintype "passive"))
    )
    (net (code "87") (name "Net-(PAD2-P)") (class "Default")
      (node (ref "C66") (pin "1") (pinfunction "1_1") (pintype "passive"))
      (node (ref "PAD2") (pin "1") (pinfunction "P_1") (pintype "passive"))
    )
    (net (code "88") (name "Net-(PAD3-P)") (class "Default")
      (node (ref "C67") (pin "1") (pinfunction "1_1") (pintype "passive"))
      (node (ref "PAD3") (pin "1") (pinfunction "P_1") (pintype "passive"))
    )
    (net (code "89") (name "Net-(PAD4-P)") (class "Default")
      (node (ref "C68") (pin "1") (pinfunction "1_1") (pintype "passive"))
      (node (ref "PAD4") (pin "1") (pinfunction "P_1") (pintype "passive"))
    )
    (net (code "90") (name "Net-(U001A-+IN)") (class "Default")
      (node (ref "R24") (pin "2") (pinfunction "2_2") (pintype "passive"))
      (node (ref "R70") (pin "1") (pinfunction "1_1") (pintype "passive"))
      (node (ref "U001") (pin "3") (pinfunction "+IN_3") (pintype "input"))
    )
    (net (code "91") (name "Net-(U001A--IN)") (class "Default")
      (node (ref "R22") (pin "1") (pinfunction "1_1") (pintype "passive"))
      (node (ref "R23") (pin "1") (pinfunction "1_1") (pintype "passive"))
      (node (ref "U001") (pin "2") (pinfunction "-IN_2") (pintype "input"))
    )
    (net (code "92") (name "Net-(U001B-+IN)") (class "Default")
      (node (ref "R27") (pin "2") (pinfunction "2_2") (pintype "passive"))
      (node (ref "U001") (pin "5") (pinfunction "+IN_5") (pintype "input"))
    )
    (net (code "93") (name "Net-(U001B--IN)") (class "Default")
      (node (ref "R25") (pin "1") (pinfunction "1_1") (pintype "passive"))
      (node (ref "R26") (pin "1") (pinfunction "1_1") (pintype "passive"))
      (node (ref "U001") (pin "6") (pinfunction "-IN_6") (pintype "input"))
    )
    (net (code "94") (name "Net-(U002A-+IN)") (class "Default")
      (node (ref "R30") (pin "2") (pinfunction "2_2") (pintype "passive"))
      (node (ref "R71") (pin "1") (pinfunction "1_1") (pintype "passive"))
      (node (ref "U002") (pin "3") (pinfunction "+IN_3") (pintype "input"))
    )
    (net (code "95") (name "Net-(U002A--IN)") (class "Default")
      (node (ref "R28") (pin "1") (pinfunction "1_1") (pintype "passive"))
      (node (ref "R29") (pin "1") (pinfunction "1_1") (pintype "passive"))
      (node (ref "U002") (pin "2") (pinfunction "-IN_2") (pintype "input"))
    )
    (net (code "96") (name "Net-(U002B-+IN)") (class "Default")
      (node (ref "R33") (pin "2") (pinfunction "2_2") (pintype "passive"))
      (node (ref "U002") (pin "5") (pinfunction "+IN_5") (pintype "input"))
    )
    (net (code "97") (name "Net-(U002B--IN)") (class "Default")
      (node (ref "R31") (pin "1") (pinfunction "1_1") (pintype "passive"))
      (node (ref "R32") (pin "1") (pinfunction "1_1") (pintype "passive"))
      (node (ref "U002") (pin "6") (pinfunction "-IN_6") (pintype "input"))
    )
    (net (code "98") (name "Net-(U003A-+IN)") (class "Default")
      (node (ref "R36") (pin "2") (pinfunction "2_2") (pintype "passive"))
      (node (ref "R72") (pin "1") (pinfunction "1_1") (pintype "passive"))
      (node (ref "U003") (pin "3") (pinfunction "+IN_3") (pintype "input"))
    )
    (net (code "99") (name "Net-(U003A--IN)") (class "Default")
      (node (ref "R34") (pin "1") (pinfunction "1_1") (pintype "passive"))
      (node (ref "R35") (pin "1") (pinfunction "1_1") (pintype "passive"))
      (node (ref "U003") (pin "2") (pinfunction "-IN_2") (pintype "input"))
    )
    (net (code "100") (name "Net-(U003B-+IN)") (class "Default")
      (node (ref "R39") (pin "2") (pinfunction "2_2") (pintype "passive"))
      (node (ref "U003") (pin "5") (pinfunction "+IN_5") (pintype "input"))
    )
    (net (code "101") (name "Net-(U003B--IN)") (class "Default")
      (node (ref "R37") (pin "1") (pinfunction "1_1") (pintype "passive"))
      (node (ref "R38") (pin "1") (pinfunction "1_1") (pintype "passive"))
      (node (ref "U003") (pin "6") (pinfunction "-IN_6") (pintype "input"))
    )
    (net (code "102") (name "Net-(U004A-+IN)") (class "Default")
      (node (ref "R42") (pin "2") (pinfunction "2_2") (pintype "passive"))
      (node (ref "U004") (pin "3") (pinfunction "+IN_3") (pintype "input"))
    )
    (net (code "103") (name "Net-(U004A--IN)") (class "Default")
      (node (ref "R40") (pin "1") (pinfunction "1_1") (pintype "passive"))
      (node (ref "R41") (pin "1") (pinfunction "1_1") (pintype "passive"))
      (node (ref "U004") (pin "2") (pinfunction "-IN_2") (pintype "input"))
    )
    (net (code "104") (name "Net-(U004B-+IN)") (class "Default")
      (node (ref "R45") (pin "2") (pinfunction "2_2") (pintype "passive"))
      (node (ref "U004") (pin "5") (pinfunction "+IN_5") (pintype "input"))
    )
    (net (code "105") (name "Net-(U004B--IN)") (class "Default")
      (node (ref "R43") (pin "1") (pinfunction "1_1") (pintype "passive"))
      (node (ref "R44") (pin "1") (pinfunction "1_1") (pintype "passive"))
      (node (ref "U004") (pin "6") (pinfunction "-IN_6") (pintype "input"))
    )
    (net (code "106") (name "Net-(U005A-+IN)") (class "Default")
      (node (ref "R50") (pin "2") (pinfunction "2_2") (pintype "passive"))
      (node (ref "U005") (pin "3") (pinfunction "+IN_3") (pintype "input"))
    )
    (net (code "107") (name "Net-(U005A--IN)") (class "Default")
      (node (ref "R48") (pin "1") (pinfunction "1_1") (pintype "passive"))
      (node (ref "R49") (pin "1") (pinfunction "1_1") (pintype "passive"))
      (node (ref "U005") (pin "2") (pinfunction "-IN_2") (pintype "input"))
    )
    (net (code "108") (name "Net-(U005B-+IN)") (class "Default")
      (node (ref "R53") (pin "2") (pinfunction "2_2") (pintype "passive"))
      (node (ref "U005") (pin "5") (pinfunction "+IN_5") (pintype "input"))
    )
    (net (code "109") (name "Net-(U005B--IN)") (class "Default")
      (node (ref "R51") (pin "1") (pinfunction "1_1") (pintype "passive"))
      (node (ref "R52") (pin "1") (pinfunction "1_1") (pintype "passive"))
      (node (ref "U005") (pin "6") (pinfunction "-IN_6") (pintype "input"))
    )
    (net (code "110") (name "Net-(U006A-+IN)") (class "Default")
      (node (ref "R56") (pin "2") (pinfunction "2_2") (pintype "passive"))
      (node (ref "U006") (pin "3") (pinfunction "+IN_3") (pintype "input"))
    )
    (net (code "111") (name "Net-(U006A--IN)") (class "Default")
      (node (ref "R54") (pin "1") (pinfunction "1_1") (pintype "passive"))
      (node (ref "R55") (pin "1") (pinfunction "1_1") (pintype "passive"))
      (node (ref "U006") (pin "2") (pinfunction "-IN_2") (pintype "input"))
    )
    (net (code "112") (name "Net-(U006B-+IN)") (class "Default")
      (node (ref "R59") (pin "2") (pinfunction "2_2") (pintype "passive"))
      (node (ref "U006") (pin "5") (pinfunction "+IN_5") (pintype "input"))
    )
    (net (code "113") (name "Net-(U006B--IN)") (class "Default")
      (node (ref "R57") (pin "1") (pinfunction "1_1") (pintype "passive"))
      (node (ref "R58") (pin "1") (pinfunction "1_1") (pintype "passive"))
      (node (ref "U006") (pin "6") (pinfunction "-IN_6") (pintype "input"))
    )
    (net (code "114") (name "Net-(U007A-+IN)") (class "Default")
      (node (ref "R62") (pin "2") (pinfunction "2_2") (pintype "passive"))
      (node (ref "U007") (pin "3") (pinfunction "+IN_3") (pintype "input"))
    )
    (net (code "115") (name "Net-(U007A--IN)") (class "Default")
      (node (ref "R60") (pin "1") (pinfunction "1_1") (pintype "passive"))
      (node (ref "R61") (pin "1") (pinfunction "1_1") (pintype "passive"))
      (node (ref "U007") (pin "2") (pinfunction "-IN_2") (pintype "input"))
    )
    (net (code "116") (name "Net-(U007B-+IN)") (class "Default")
      (node (ref "R65") (pin "2") (pinfunction "2_2") (pintype "passive"))
      (node (ref "U007") (pin "5") (pinfunction "+IN_5") (pintype "input"))
    )
    (net (code "117") (name "Net-(U007B--IN)") (class "Default")
      (node (ref "R63") (pin "1") (pinfunction "1_1") (pintype "passive"))
      (node (ref "R64") (pin "1") (pinfunction "1_1") (pintype "passive"))
      (node (ref "U007") (pin "6") (pinfunction "-IN_6") (pintype "input"))
    )
    (net (code "118") (name "Net-(U009A-+IN)") (class "Default")
      (node (ref "R69") (pin "1") (pinfunction "1_1") (pintype "passive"))
      (node (ref "R77") (pin "2") (pinfunction "2_2") (pintype "passive"))
      (node (ref "U009") (pin "3") (pinfunction "+IN_3") (pintype "input"))
    )
    (net (code "119") (name "Net-(U009A--IN)") (class "Default")
      (node (ref "R75") (pin "1") (pinfunction "1_1") (pintype "passive"))
      (node (ref "R76") (pin "1") (pinfunction "1_1") (pintype "passive"))
      (node (ref "U009") (pin "2") (pinfunction "-IN_2") (pintype "input"))
    )
    (net (code "120") (name "Net-(U009B-+IN)") (class "Default")
      (node (ref "R81") (pin "2") (pinfunction "2_2") (pintype "passive"))
      (node (ref "U009") (pin "5") (pinfunction "+IN_5") (pintype "input"))
    )
    (net (code "121") (name "Net-(U009B--IN)") (class "Default")
      (node (ref "R79") (pin "1") (pinfunction "1_1") (pintype "passive"))
      (node (ref "R80") (pin "1") (pinfunction "1_1") (pintype "passive"))
      (node (ref "U009") (pin "6") (pinfunction "-IN_6") (pintype "input"))
    )
    (net (code "122") (name "RF1") (class "Default")
      (node (ref "IC1") (pin "1") (pinfunction "I0_1") (pintype "input"))
      (node (ref "IC1") (pin "9") (pinfunction "I0_9") (pintype "input"))
      (node (ref "IC2") (pin "1") (pinfunction "I_1") (pintype "input"))
      (node (ref "R21") (pin "2") (pinfunction "2_2") (pintype "passive"))
      (node (ref "X18") (pin "1") (pinfunction "1_1") (pintype "passive"))
    )
    (net (code "123") (name "RF3") (class "Default")
      (node (ref "IC2") (pin "3") (pinfunction "I_3") (pintype "input"))
      (node (ref "IC3") (pin "1") (pinfunction "I0_1") (pintype "input"))
      (node (ref "IC3") (pin "9") (pinfunction "I0_9") (pintype "input"))
      (node (ref "R66") (pin "2") (pinfunction "2_2") (pintype "passive"))
      (node (ref "X27") (pin "1") (pinfunction "1_1") (pintype "passive"))
    )
    (net (code "124") (name "RF5") (class "Default")
      (node (ref "IC4") (pin "1") (pinfunction "I0_1") (pintype "input"))
      (node (ref "IC4") (pin "9") (pinfunction "I0_9") (pintype "input"))
      (node (ref "IC6") (pin "1") (pinfunction "I_1") (pintype "input"))
      (node (ref "R67") (pin "2") (pinfunction "2_2") (pintype "passive"))
      (node (ref "X28") (pin "1") (pinfunction "1_1") (pintype "passive"))
    )
    (net (code "125") (name "RF7") (class "Default")
      (node (ref "IC5") (pin "1") (pinfunction "I0_1") (pintype "input"))
      (node (ref "IC5") (pin "9") (pinfunction "I0_9") (pintype "input"))
      (node (ref "IC6") (pin "3") (pinfunction "I_3") (pintype "input"))
      (node (ref "R68") (pin "2") (pinfunction "2_2") (pintype "passive"))
      (node (ref "X29") (pin "1") (pinfunction "1_1") (pintype "passive"))
    )
    (net (code "126") (name "THSD") (class "Default")
      (node (ref "R1") (pin "1") (pinfunction "1_1") (pintype "passive"))
      (node (ref "SV3") (pin "1") (pinfunction "1_1") (pintype "passive"))
    )
    (net (code "127") (name "VDDM") (class "Default")
      (node (ref "C2") (pin "1") (pinfunction "1_1") (pintype "passive"))
      (node (ref "C24") (pin "1") (pinfunction "1_1") (pintype "passive"))
      (node (ref "C32") (pin "2") (pinfunction "2_2") (pintype "passive"))
      (node (ref "C36") (pin "2") (pinfunction "2_2") (pintype "passive"))
      (node (ref "C40") (pin "2") (pinfunction "2_2") (pintype "passive"))
      (node (ref "C44") (pin "2") (pinfunction "2_2") (pintype "passive"))
      (node (ref "C48") (pin "2") (pinfunction "2_2") (pintype "passive"))
      (node (ref "C54") (pin "2") (pinfunction "2_2") (pintype "passive"))
      (node (ref "C56") (pin "2") (pinfunction "2_2") (pintype "passive"))
      (node (ref "C60") (pin "2") (pinfunction "2_2") (pintype "passive"))
      (node (ref "D3") (pin "A") (pinfunction "A_A") (pintype "passive"))
      (node (ref "R46") (pin "1") (pinfunction "1_1") (pintype "passive"))
      (node (ref "SV3") (pin "3") (pinfunction "3_3") (pintype "passive"))
      (node (ref "U001") (pin "4") (pinfunction "VSS_4") (pintype "power_in"))
      (node (ref "U002") (pin "4") (pinfunction "VSS_4") (pintype "power_in"))
      (node (ref "U003") (pin "4") (pinfunction "VSS_4") (pintype "power_in"))
      (node (ref "U004") (pin "4") (pinfunction "VSS_4") (pintype "power_in"))
      (node (ref "U005") (pin "4") (pinfunction "VSS_4") (pintype "power_in"))
      (node (ref "U006") (pin "4") (pinfunction "VSS_4") (pintype "power_in"))
      (node (ref "U007") (pin "4") (pinfunction "VSS_4") (pintype "power_in"))
      (node (ref "U009") (pin "4") (pinfunction "VSS_4") (pintype "power_in"))
    )
    (net (code "128") (name "VDDP") (class "Default")
      (node (ref "C1") (pin "1") (pinfunction "1_1") (pintype "passive"))
      (node (ref "C23") (pin "1") (pinfunction "1_1") (pintype "passive"))
      (node (ref "C27") (pin "1") (pinfunction "1_1") (pintype "passive"))
      (node (ref "C28") (pin "1") (pinfunction "1_1") (pintype "passive"))
      (node (ref "C29") (pin "1") (pinfunction "1_1") (pintype "passive"))
      (node (ref "C33") (pin "1") (pinfunction "1_1") (pintype "passive"))
      (node (ref "C37") (pin "1") (pinfunction "1_1") (pintype "passive"))
      (node (ref "C41") (pin "1") (pinfunction "1_1") (pintype "passive"))
      (node (ref "C45") (pin "1") (pinfunction "1_1") (pintype "passive"))
      (node (ref "C49") (pin "1") (pinfunction "1_1") (pintype "passive"))
      (node (ref "C5") (pin "1") (pinfunction "1_1") (pintype "passive"))
      (node (ref "C55") (pin "1") (pinfunction "1_1") (pintype "passive"))
      (node (ref "C57") (pin "1") (pinfunction "1_1") (pintype "passive"))
      (node (ref "C6") (pin "1") (pinfunction "1_1") (pintype "passive"))
      (node (ref "C61") (pin "1") (pinfunction "1_1") (pintype "passive"))
      (node (ref "C62") (pin "1") (pinfunction "1_1") (pintype "passive"))
      (node (ref "D1") (pin "C") (pinfunction "C_C") (pintype "passive"))
      (node (ref "IC1") (pin "14") (pinfunction "VCC_14") (pintype "power_in"))
      (node (ref "IC2") (pin "14") (pinfunction "VCC_14") (pintype "power_in"))
      (node (ref "IC3") (pin "14") (pinfunction "VCC_14") (pintype "power_in"))
      (node (ref "IC4") (pin "14") (pinfunction "VCC_14") (pintype "power_in"))
      (node (ref "IC5") (pin "14") (pinfunction "VCC_14") (pintype "power_in"))
      (node (ref "IC6") (pin "14") (pinfunction "VCC_14") (pintype "power_in"))
      (node (ref "JP1") (pin "3") (pinfunction "1_3") (pintype "passive"))
      (node (ref "LED1") (pin "A") (pinfunction "A_A") (pintype "passive"))
      (node (ref "R1") (pin "2") (pinfunction "2_2") (pintype "passive"))
      (node (ref "SV3") (pin "12") (pinfunction "12_12") (pintype "passive"))
      (node (ref "SV3") (pin "2") (pinfunction "2_2") (pintype "passive"))
      (node (ref "U001") (pin "8") (pinfunction "VDD_8") (pintype "power_in"))
      (node (ref "U002") (pin "8") (pinfunction "VDD_8") (pintype "power_in"))
      (node (ref "U003") (pin "8") (pinfunction "VDD_8") (pintype "power_in"))
      (node (ref "U004") (pin "8") (pinfunction "VDD_8") (pintype "power_in"))
      (node (ref "U005") (pin "8") (pinfunction "VDD_8") (pintype "power_in"))
      (node (ref "U006") (pin "8") (pinfunction "VDD_8") (pintype "power_in"))
      (node (ref "U007") (pin "8") (pinfunction "VDD_8") (pintype "power_in"))
      (node (ref "U009") (pin "8") (pinfunction "VDD_8") (pintype "power_in"))
    )
    (net (code "129") (name "XDCR_1") (class "Default")
      (node (ref "C11") (pin "1") (pinfunction "1_1") (pintype "passive"))
      (node (ref "C15") (pin "1") (pinfunction "1_1") (pintype "passive"))
      (node (ref "R12") (pin "2") (pinfunction "2_2") (pintype "passive"))
      (node (ref "R8") (pin "2") (pinfunction "2_2") (pintype "passive"))
      (node (ref "SV1") (pin "1") (pinfunction "1_1") (pintype "passive"))
      (node (ref "X5") (pin "1") (pinfunction "1_1") (pintype "passive"))
      (node (ref "X9") (pin "1") (pinfunction "1_1") (pintype "passive"))
    )
    (net (code "130") (name "XDCR_2") (class "Default")
      (node (ref "C11") (pin "2") (pinfunction "2_2") (pintype "passive"))
      (node (ref "C16") (pin "1") (pinfunction "1_1") (pintype "passive"))
      (node (ref "R13") (pin "2") (pinfunction "2_2") (pintype "passive"))
      (node (ref "R8") (pin "1") (pinfunction "1_1") (pintype "passive"))
      (node (ref "SV1") (pin "2") (pinfunction "2_2") (pintype "passive"))
      (node (ref "X10") (pin "1") (pinfunction "1_1") (pintype "passive"))
      (node (ref "X5") (pin "2") (pinfunction "2_2") (pintype "passive"))
      (node (ref "X5") (pin "3") (pinfunction "2_3") (pintype "passive"))
      (node (ref "X5") (pin "4") (pinfunction "2_4") (pintype "passive"))
      (node (ref "X5") (pin "5") (pinfunction "2_5") (pintype "passive"))
    )
    (net (code "131") (name "XDCR_3") (class "Default")
      (node (ref "C12") (pin "1") (pinfunction "1_1") (pintype "passive"))
      (node (ref "C17") (pin "1") (pinfunction "1_1") (pintype "passive"))
      (node (ref "R14") (pin "2") (pinfunction "2_2") (pintype "passive"))
      (node (ref "R9") (pin "2") (pinfunction "2_2") (pintype "passive"))
      (node (ref "SV1") (pin "3") (pinfunction "3_3") (pintype "passive"))
      (node (ref "X11") (pin "1") (pinfunction "1_1") (pintype "passive"))
      (node (ref "X6") (pin "1") (pinfunction "1_1") (pintype "passive"))
    )
    (net (code "132") (name "XDCR_4") (class "Default")
      (node (ref "C12") (pin "2") (pinfunction "2_2") (pintype "passive"))
      (node (ref "C18") (pin "1") (pinfunction "1_1") (pintype "passive"))
      (node (ref "R15") (pin "2") (pinfunction "2_2") (pintype "passive"))
      (node (ref "R9") (pin "1") (pinfunction "1_1") (pintype "passive"))
      (node (ref "SV1") (pin "4") (pinfunction "4_4") (pintype "passive"))
      (node (ref "X12") (pin "1") (pinfunction "1_1") (pintype "passive"))
      (node (ref "X6") (pin "2") (pinfunction "2_2") (pintype "passive"))
      (node (ref "X6") (pin "3") (pinfunction "2_3") (pintype "passive"))
      (node (ref "X6") (pin "4") (pinfunction "2_4") (pintype "passive"))
      (node (ref "X6") (pin "5") (pinfunction "2_5") (pintype "passive"))
    )
    (net (code "133") (name "XDCR_5") (class "Default")
      (node (ref "C13") (pin "1") (pinfunction "1_1") (pintype "passive"))
      (node (ref "C19") (pin "1") (pinfunction "1_1") (pintype "passive"))
      (node (ref "R10") (pin "2") (pinfunction "2_2") (pintype "passive"))
      (node (ref "R16") (pin "2") (pinfunction "2_2") (pintype "passive"))
      (node (ref "SV1") (pin "11") (pinfunction "11_11") (pintype "passive"))
      (node (ref "X13") (pin "1") (pinfunction "1_1") (pintype "passive"))
      (node (ref "X7") (pin "1") (pinfunction "1_1") (pintype "passive"))
    )
    (net (code "134") (name "XDCR_6") (class "Default")
      (node (ref "C13") (pin "2") (pinfunction "2_2") (pintype "passive"))
      (node (ref "C20") (pin "1") (pinfunction "1_1") (pintype "passive"))
      (node (ref "R10") (pin "1") (pinfunction "1_1") (pintype "passive"))
      (node (ref "R17") (pin "2") (pinfunction "2_2") (pintype "passive"))
      (node (ref "SV1") (pin "12") (pinfunction "12_12") (pintype "passive"))
      (node (ref "X14") (pin "1") (pinfunction "1_1") (pintype "passive"))
      (node (ref "X7") (pin "2") (pinfunction "2_2") (pintype "passive"))
      (node (ref "X7") (pin "3") (pinfunction "2_3") (pintype "passive"))
      (node (ref "X7") (pin "4") (pinfunction "2_4") (pintype "passive"))
      (node (ref "X7") (pin "5") (pinfunction "2_5") (pintype "passive"))
    )
    (net (code "135") (name "XDCR_7") (class "Default")
      (node (ref "C14") (pin "1") (pinfunction "1_1") (pintype "passive"))
      (node (ref "C21") (pin "1") (pinfunction "1_1") (pintype "passive"))
      (node (ref "R11") (pin "2") (pinfunction "2_2") (pintype "passive"))
      (node (ref "R18") (pin "2") (pinfunction "2_2") (pintype "passive"))
      (node (ref "SV1") (pin "13") (pinfunction "13_13") (pintype "passive"))
      (node (ref "X15") (pin "1") (pinfunction "1_1") (pintype "passive"))
      (node (ref "X8") (pin "1") (pinfunction "1_1") (pintype "passive"))
    )
    (net (code "136") (name "XDCR_8") (class "Default")
      (node (ref "C14") (pin "2") (pinfunction "2_2") (pintype "passive"))
      (node (ref "C22") (pin "1") (pinfunction "1_1") (pintype "passive"))
      (node (ref "R11") (pin "1") (pinfunction "1_1") (pintype "passive"))
      (node (ref "R19") (pin "2") (pinfunction "2_2") (pintype "passive"))
      (node (ref "SV1") (pin "14") (pinfunction "14_14") (pintype "passive"))
      (node (ref "X16") (pin "1") (pinfunction "1_1") (pintype "passive"))
      (node (ref "X8") (pin "2") (pinfunction "2_2") (pintype "passive"))
      (node (ref "X8") (pin "3") (pinfunction "2_3") (pintype "passive"))
      (node (ref "X8") (pin "4") (pinfunction "2_4") (pintype "passive"))
      (node (ref "X8") (pin "5") (pinfunction "2_5") (pintype "passive"))
    )
    (net (code "137") (name "~{RF1}") (class "Default")
      (node (ref "IC1") (pin "12") (pinfunction "I0_12") (pintype "input"))
      (node (ref "IC1") (pin "4") (pinfunction "I0_4") (pintype "input"))
      (node (ref "IC2") (pin "2") (pinfunction "O_2") (pintype "output"))
    )
    (net (code "138") (name "~{RF3}") (class "Default")
      (node (ref "IC2") (pin "4") (pinfunction "O_4") (pintype "output"))
      (node (ref "IC3") (pin "12") (pinfunction "I0_12") (pintype "input"))
      (node (ref "IC3") (pin "4") (pinfunction "I0_4") (pintype "input"))
    )
    (net (code "139") (name "~{RF5}") (class "Default")
      (node (ref "IC4") (pin "12") (pinfunction "I0_12") (pintype "input"))
      (node (ref "IC4") (pin "4") (pinfunction "I0_4") (pintype "input"))
      (node (ref "IC6") (pin "2") (pinfunction "O_2") (pintype "output"))
    )
    (net (code "140") (name "~{RF7}") (class "Default")
      (node (ref "IC5") (pin "12") (pinfunction "I0_12") (pintype "input"))
      (node (ref "IC5") (pin "4") (pinfunction "I0_4") (pintype "input"))
      (node (ref "IC6") (pin "4") (pinfunction "O_4") (pintype "output"))
    )
  )
)
